# KeyBoard_LED.net
KiCad netlist of a schematic drawn in Altium Designer
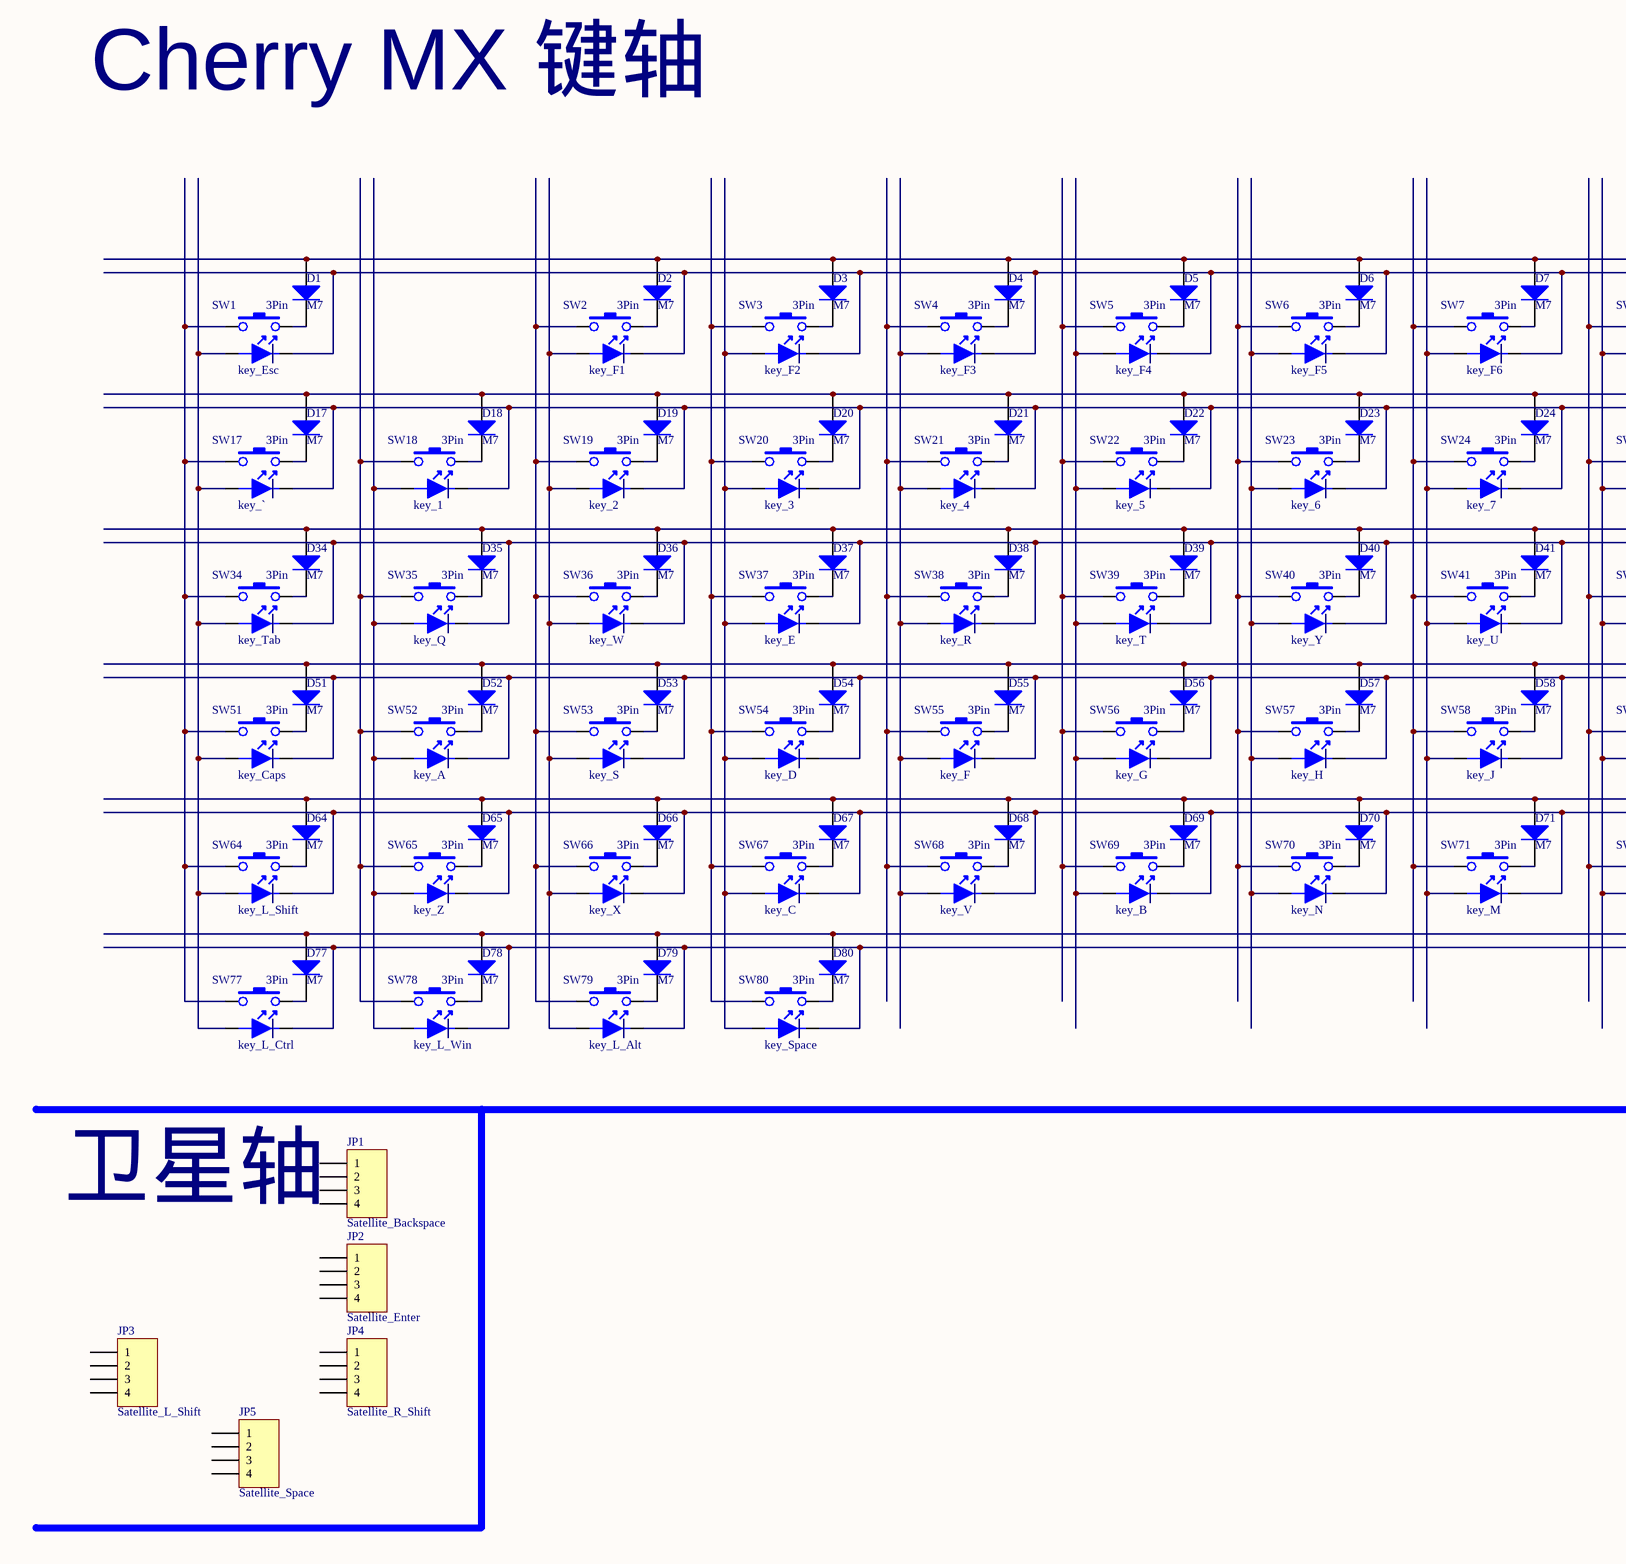
[diagram p0: KeyBoard_LED.SchDoc, left]
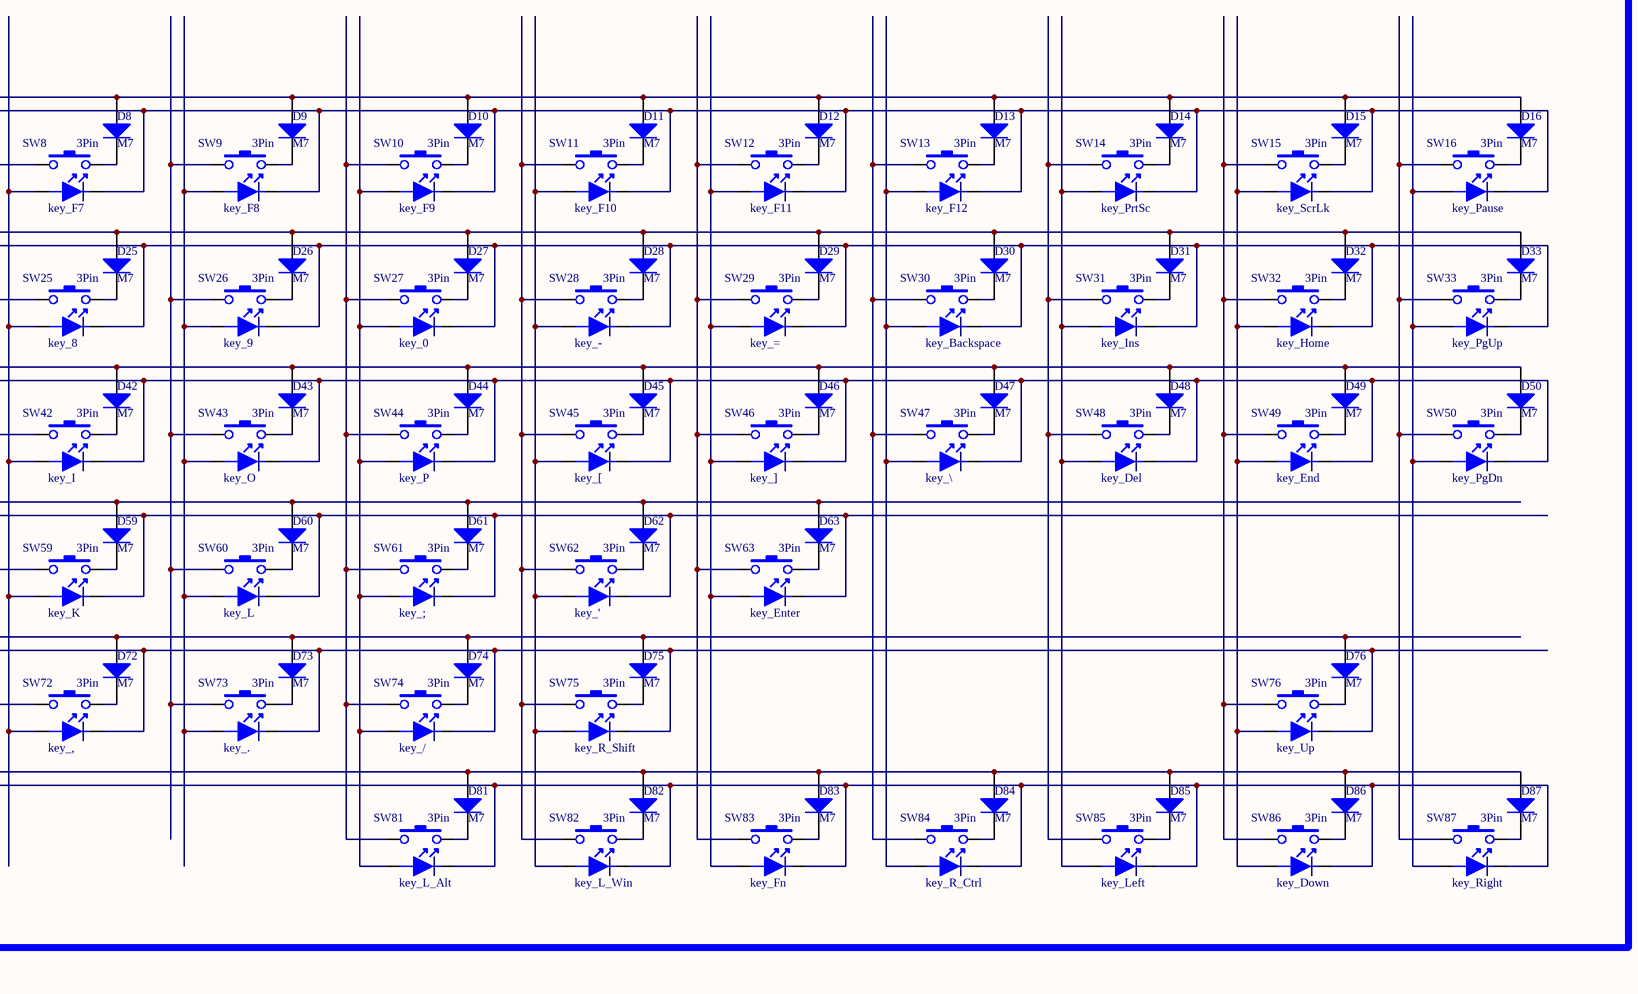
[diagram p1: KeyBoard_LED.SchDoc, right]

(export (version "E")
  (design (tool "Eeschema 10.0.6"))
  (components
    (comp (ref "D1")
      (value "M7")
      (footprint "SMA(DO-214AC)_S1")
      (description "二极管")
      (libsource (lib "Miscellaneous Devices LC") (part "SMA(DO-214AC) M7"))
    )
    (comp (ref "D2")
      (value "M7")
      (footprint "SMA(DO-214AC)_S1")
      (description "二极管")
      (libsource (lib "Miscellaneous Devices LC") (part "SMA(DO-214AC) M7"))
    )
    (comp (ref "D3")
      (value "M7")
      (footprint "SMA(DO-214AC)_S1")
      (description "二极管")
      (libsource (lib "Miscellaneous Devices LC") (part "SMA(DO-214AC) M7"))
    )
    (comp (ref "D4")
      (value "M7")
      (footprint "SMA(DO-214AC)_S1")
      (description "二极管")
      (libsource (lib "Miscellaneous Devices LC") (part "SMA(DO-214AC) M7"))
    )
    (comp (ref "D5")
      (value "M7")
      (footprint "SMA(DO-214AC)_S1")
      (description "二极管")
      (libsource (lib "Miscellaneous Devices LC") (part "SMA(DO-214AC) M7"))
    )
    (comp (ref "D6")
      (value "M7")
      (footprint "SMA(DO-214AC)_S1")
      (description "二极管")
      (libsource (lib "Miscellaneous Devices LC") (part "SMA(DO-214AC) M7"))
    )
    (comp (ref "D7")
      (value "M7")
      (footprint "SMA(DO-214AC)_S1")
      (description "二极管")
      (libsource (lib "Miscellaneous Devices LC") (part "SMA(DO-214AC) M7"))
    )
    (comp (ref "D8")
      (value "M7")
      (footprint "SMA(DO-214AC)_S1")
      (description "二极管")
      (libsource (lib "Miscellaneous Devices LC") (part "SMA(DO-214AC) M7"))
    )
    (comp (ref "D9")
      (value "M7")
      (footprint "SMA(DO-214AC)_S1")
      (description "二极管")
      (libsource (lib "Miscellaneous Devices LC") (part "SMA(DO-214AC) M7"))
    )
    (comp (ref "D10")
      (value "M7")
      (footprint "SMA(DO-214AC)_S1")
      (description "二极管")
      (libsource (lib "Miscellaneous Devices LC") (part "SMA(DO-214AC) M7"))
    )
    (comp (ref "D11")
      (value "M7")
      (footprint "SMA(DO-214AC)_S1")
      (description "二极管")
      (libsource (lib "Miscellaneous Devices LC") (part "SMA(DO-214AC) M7"))
    )
    (comp (ref "D12")
      (value "M7")
      (footprint "SMA(DO-214AC)_S1")
      (description "二极管")
      (libsource (lib "Miscellaneous Devices LC") (part "SMA(DO-214AC) M7"))
    )
    (comp (ref "D13")
      (value "M7")
      (footprint "SMA(DO-214AC)_S1")
      (description "二极管")
      (libsource (lib "Miscellaneous Devices LC") (part "SMA(DO-214AC) M7"))
    )
    (comp (ref "D14")
      (value "M7")
      (footprint "SMA(DO-214AC)_S1")
      (description "二极管")
      (libsource (lib "Miscellaneous Devices LC") (part "SMA(DO-214AC) M7"))
    )
    (comp (ref "D15")
      (value "M7")
      (footprint "SMA(DO-214AC)_S1")
      (description "二极管")
      (libsource (lib "Miscellaneous Devices LC") (part "SMA(DO-214AC) M7"))
    )
    (comp (ref "D16")
      (value "M7")
      (footprint "SMA(DO-214AC)_S1")
      (description "二极管")
      (libsource (lib "Miscellaneous Devices LC") (part "SMA(DO-214AC) M7"))
    )
    (comp (ref "D17")
      (value "M7")
      (footprint "SMA(DO-214AC)_S1")
      (description "二极管")
      (libsource (lib "Miscellaneous Devices LC") (part "SMA(DO-214AC) M7"))
    )
    (comp (ref "D18")
      (value "M7")
      (footprint "SMA(DO-214AC)_S1")
      (description "二极管")
      (libsource (lib "Miscellaneous Devices LC") (part "SMA(DO-214AC) M7"))
    )
    (comp (ref "D19")
      (value "M7")
      (footprint "SMA(DO-214AC)_S1")
      (description "二极管")
      (libsource (lib "Miscellaneous Devices LC") (part "SMA(DO-214AC) M7"))
    )
    (comp (ref "D20")
      (value "M7")
      (footprint "SMA(DO-214AC)_S1")
      (description "二极管")
      (libsource (lib "Miscellaneous Devices LC") (part "SMA(DO-214AC) M7"))
    )
    (comp (ref "D21")
      (value "M7")
      (footprint "SMA(DO-214AC)_S1")
      (description "二极管")
      (libsource (lib "Miscellaneous Devices LC") (part "SMA(DO-214AC) M7"))
    )
    (comp (ref "D22")
      (value "M7")
      (footprint "SMA(DO-214AC)_S1")
      (description "二极管")
      (libsource (lib "Miscellaneous Devices LC") (part "SMA(DO-214AC) M7"))
    )
    (comp (ref "D23")
      (value "M7")
      (footprint "SMA(DO-214AC)_S1")
      (description "二极管")
      (libsource (lib "Miscellaneous Devices LC") (part "SMA(DO-214AC) M7"))
    )
    (comp (ref "D24")
      (value "M7")
      (footprint "SMA(DO-214AC)_S1")
      (description "二极管")
      (libsource (lib "Miscellaneous Devices LC") (part "SMA(DO-214AC) M7"))
    )
    (comp (ref "D25")
      (value "M7")
      (footprint "SMA(DO-214AC)_S1")
      (description "二极管")
      (libsource (lib "Miscellaneous Devices LC") (part "SMA(DO-214AC) M7"))
    )
    (comp (ref "D26")
      (value "M7")
      (footprint "SMA(DO-214AC)_S1")
      (description "二极管")
      (libsource (lib "Miscellaneous Devices LC") (part "SMA(DO-214AC) M7"))
    )
    (comp (ref "D27")
      (value "M7")
      (footprint "SMA(DO-214AC)_S1")
      (description "二极管")
      (libsource (lib "Miscellaneous Devices LC") (part "SMA(DO-214AC) M7"))
    )
    (comp (ref "D28")
      (value "M7")
      (footprint "SMA(DO-214AC)_S1")
      (description "二极管")
      (libsource (lib "Miscellaneous Devices LC") (part "SMA(DO-214AC) M7"))
    )
    (comp (ref "D29")
      (value "M7")
      (footprint "SMA(DO-214AC)_S1")
      (description "二极管")
      (libsource (lib "Miscellaneous Devices LC") (part "SMA(DO-214AC) M7"))
    )
    (comp (ref "D30")
      (value "M7")
      (footprint "SMA(DO-214AC)_S1")
      (description "二极管")
      (libsource (lib "Miscellaneous Devices LC") (part "SMA(DO-214AC) M7"))
    )
    (comp (ref "D31")
      (value "M7")
      (footprint "SMA(DO-214AC)_S1")
      (description "二极管")
      (libsource (lib "Miscellaneous Devices LC") (part "SMA(DO-214AC) M7"))
    )
    (comp (ref "D32")
      (value "M7")
      (footprint "SMA(DO-214AC)_S1")
      (description "二极管")
      (libsource (lib "Miscellaneous Devices LC") (part "SMA(DO-214AC) M7"))
    )
    (comp (ref "D33")
      (value "M7")
      (footprint "SMA(DO-214AC)_S1")
      (description "二极管")
      (libsource (lib "Miscellaneous Devices LC") (part "SMA(DO-214AC) M7"))
    )
    (comp (ref "D34")
      (value "M7")
      (footprint "SMA(DO-214AC)_S1")
      (description "二极管")
      (libsource (lib "Miscellaneous Devices LC") (part "SMA(DO-214AC) M7"))
    )
    (comp (ref "D35")
      (value "M7")
      (footprint "SMA(DO-214AC)_S1")
      (description "二极管")
      (libsource (lib "Miscellaneous Devices LC") (part "SMA(DO-214AC) M7"))
    )
    (comp (ref "D36")
      (value "M7")
      (footprint "SMA(DO-214AC)_S1")
      (description "二极管")
      (libsource (lib "Miscellaneous Devices LC") (part "SMA(DO-214AC) M7"))
    )
    (comp (ref "D37")
      (value "M7")
      (footprint "SMA(DO-214AC)_S1")
      (description "二极管")
      (libsource (lib "Miscellaneous Devices LC") (part "SMA(DO-214AC) M7"))
    )
    (comp (ref "D38")
      (value "M7")
      (footprint "SMA(DO-214AC)_S1")
      (description "二极管")
      (libsource (lib "Miscellaneous Devices LC") (part "SMA(DO-214AC) M7"))
    )
    (comp (ref "D39")
      (value "M7")
      (footprint "SMA(DO-214AC)_S1")
      (description "二极管")
      (libsource (lib "Miscellaneous Devices LC") (part "SMA(DO-214AC) M7"))
    )
    (comp (ref "D40")
      (value "M7")
      (footprint "SMA(DO-214AC)_S1")
      (description "二极管")
      (libsource (lib "Miscellaneous Devices LC") (part "SMA(DO-214AC) M7"))
    )
    (comp (ref "D41")
      (value "M7")
      (footprint "SMA(DO-214AC)_S1")
      (description "二极管")
      (libsource (lib "Miscellaneous Devices LC") (part "SMA(DO-214AC) M7"))
    )
    (comp (ref "D42")
      (value "M7")
      (footprint "SMA(DO-214AC)_S1")
      (description "二极管")
      (libsource (lib "Miscellaneous Devices LC") (part "SMA(DO-214AC) M7"))
    )
    (comp (ref "D43")
      (value "M7")
      (footprint "SMA(DO-214AC)_S1")
      (description "二极管")
      (libsource (lib "Miscellaneous Devices LC") (part "SMA(DO-214AC) M7"))
    )
    (comp (ref "D44")
      (value "M7")
      (footprint "SMA(DO-214AC)_S1")
      (description "二极管")
      (libsource (lib "Miscellaneous Devices LC") (part "SMA(DO-214AC) M7"))
    )
    (comp (ref "D45")
      (value "M7")
      (footprint "SMA(DO-214AC)_S1")
      (description "二极管")
      (libsource (lib "Miscellaneous Devices LC") (part "SMA(DO-214AC) M7"))
    )
    (comp (ref "D46")
      (value "M7")
      (footprint "SMA(DO-214AC)_S1")
      (description "二极管")
      (libsource (lib "Miscellaneous Devices LC") (part "SMA(DO-214AC) M7"))
    )
    (comp (ref "D47")
      (value "M7")
      (footprint "SMA(DO-214AC)_S1")
      (description "二极管")
      (libsource (lib "Miscellaneous Devices LC") (part "SMA(DO-214AC) M7"))
    )
    (comp (ref "D48")
      (value "M7")
      (footprint "SMA(DO-214AC)_S1")
      (description "二极管")
      (libsource (lib "Miscellaneous Devices LC") (part "SMA(DO-214AC) M7"))
    )
    (comp (ref "D49")
      (value "M7")
      (footprint "SMA(DO-214AC)_S1")
      (description "二极管")
      (libsource (lib "Miscellaneous Devices LC") (part "SMA(DO-214AC) M7"))
    )
    (comp (ref "D50")
      (value "M7")
      (footprint "SMA(DO-214AC)_S1")
      (description "二极管")
      (libsource (lib "Miscellaneous Devices LC") (part "SMA(DO-214AC) M7"))
    )
    (comp (ref "D51")
      (value "M7")
      (footprint "SMA(DO-214AC)_S1")
      (description "二极管")
      (libsource (lib "Miscellaneous Devices LC") (part "SMA(DO-214AC) M7"))
    )
    (comp (ref "D52")
      (value "M7")
      (footprint "SMA(DO-214AC)_S1")
      (description "二极管")
      (libsource (lib "Miscellaneous Devices LC") (part "SMA(DO-214AC) M7"))
    )
    (comp (ref "D53")
      (value "M7")
      (footprint "SMA(DO-214AC)_S1")
      (description "二极管")
      (libsource (lib "Miscellaneous Devices LC") (part "SMA(DO-214AC) M7"))
    )
    (comp (ref "D54")
      (value "M7")
      (footprint "SMA(DO-214AC)_S1")
      (description "二极管")
      (libsource (lib "Miscellaneous Devices LC") (part "SMA(DO-214AC) M7"))
    )
    (comp (ref "D55")
      (value "M7")
      (footprint "SMA(DO-214AC)_S1")
      (description "二极管")
      (libsource (lib "Miscellaneous Devices LC") (part "SMA(DO-214AC) M7"))
    )
    (comp (ref "D56")
      (value "M7")
      (footprint "SMA(DO-214AC)_S1")
      (description "二极管")
      (libsource (lib "Miscellaneous Devices LC") (part "SMA(DO-214AC) M7"))
    )
    (comp (ref "D57")
      (value "M7")
      (footprint "SMA(DO-214AC)_S1")
      (description "二极管")
      (libsource (lib "Miscellaneous Devices LC") (part "SMA(DO-214AC) M7"))
    )
    (comp (ref "D58")
      (value "M7")
      (footprint "SMA(DO-214AC)_S1")
      (description "二极管")
      (libsource (lib "Miscellaneous Devices LC") (part "SMA(DO-214AC) M7"))
    )
    (comp (ref "D59")
      (value "M7")
      (footprint "SMA(DO-214AC)_S1")
      (description "二极管")
      (libsource (lib "Miscellaneous Devices LC") (part "SMA(DO-214AC) M7"))
    )
    (comp (ref "D60")
      (value "M7")
      (footprint "SMA(DO-214AC)_S1")
      (description "二极管")
      (libsource (lib "Miscellaneous Devices LC") (part "SMA(DO-214AC) M7"))
    )
    (comp (ref "D61")
      (value "M7")
      (footprint "SMA(DO-214AC)_S1")
      (description "二极管")
      (libsource (lib "Miscellaneous Devices LC") (part "SMA(DO-214AC) M7"))
    )
    (comp (ref "D62")
      (value "M7")
      (footprint "SMA(DO-214AC)_S1")
      (description "二极管")
      (libsource (lib "Miscellaneous Devices LC") (part "SMA(DO-214AC) M7"))
    )
    (comp (ref "D63")
      (value "M7")
      (footprint "SMA(DO-214AC)_S1")
      (description "二极管")
      (libsource (lib "Miscellaneous Devices LC") (part "SMA(DO-214AC) M7"))
    )
    (comp (ref "D64")
      (value "M7")
      (footprint "SMA(DO-214AC)_S1")
      (description "二极管")
      (libsource (lib "Miscellaneous Devices LC") (part "SMA(DO-214AC) M7"))
    )
    (comp (ref "D65")
      (value "M7")
      (footprint "SMA(DO-214AC)_S1")
      (description "二极管")
      (libsource (lib "Miscellaneous Devices LC") (part "SMA(DO-214AC) M7"))
    )
    (comp (ref "D66")
      (value "M7")
      (footprint "SMA(DO-214AC)_S1")
      (description "二极管")
      (libsource (lib "Miscellaneous Devices LC") (part "SMA(DO-214AC) M7"))
    )
    (comp (ref "D67")
      (value "M7")
      (footprint "SMA(DO-214AC)_S1")
      (description "二极管")
      (libsource (lib "Miscellaneous Devices LC") (part "SMA(DO-214AC) M7"))
    )
    (comp (ref "D68")
      (value "M7")
      (footprint "SMA(DO-214AC)_S1")
      (description "二极管")
      (libsource (lib "Miscellaneous Devices LC") (part "SMA(DO-214AC) M7"))
    )
    (comp (ref "D69")
      (value "M7")
      (footprint "SMA(DO-214AC)_S1")
      (description "二极管")
      (libsource (lib "Miscellaneous Devices LC") (part "SMA(DO-214AC) M7"))
    )
    (comp (ref "D70")
      (value "M7")
      (footprint "SMA(DO-214AC)_S1")
      (description "二极管")
      (libsource (lib "Miscellaneous Devices LC") (part "SMA(DO-214AC) M7"))
    )
    (comp (ref "D71")
      (value "M7")
      (footprint "SMA(DO-214AC)_S1")
      (description "二极管")
      (libsource (lib "Miscellaneous Devices LC") (part "SMA(DO-214AC) M7"))
    )
    (comp (ref "D72")
      (value "M7")
      (footprint "SMA(DO-214AC)_S1")
      (description "二极管")
      (libsource (lib "Miscellaneous Devices LC") (part "SMA(DO-214AC) M7"))
    )
    (comp (ref "D73")
      (value "M7")
      (footprint "SMA(DO-214AC)_S1")
      (description "二极管")
      (libsource (lib "Miscellaneous Devices LC") (part "SMA(DO-214AC) M7"))
    )
    (comp (ref "D74")
      (value "M7")
      (footprint "SMA(DO-214AC)_S1")
      (description "二极管")
      (libsource (lib "Miscellaneous Devices LC") (part "SMA(DO-214AC) M7"))
    )
    (comp (ref "D75")
      (value "M7")
      (footprint "SMA(DO-214AC)_S1")
      (description "二极管")
      (libsource (lib "Miscellaneous Devices LC") (part "SMA(DO-214AC) M7"))
    )
    (comp (ref "D76")
      (value "M7")
      (footprint "SMA(DO-214AC)_S1")
      (description "二极管")
      (libsource (lib "Miscellaneous Devices LC") (part "SMA(DO-214AC) M7"))
    )
    (comp (ref "D77")
      (value "M7")
      (footprint "SMA(DO-214AC)_S1")
      (description "二极管")
      (libsource (lib "Miscellaneous Devices LC") (part "SMA(DO-214AC) M7"))
    )
    (comp (ref "D78")
      (value "M7")
      (footprint "SMA(DO-214AC)_S1")
      (description "二极管")
      (libsource (lib "Miscellaneous Devices LC") (part "SMA(DO-214AC) M7"))
    )
    (comp (ref "D79")
      (value "M7")
      (footprint "SMA(DO-214AC)_S1")
      (description "二极管")
      (libsource (lib "Miscellaneous Devices LC") (part "SMA(DO-214AC) M7"))
    )
    (comp (ref "D80")
      (value "M7")
      (footprint "SMA(DO-214AC)_S1")
      (description "二极管")
      (libsource (lib "Miscellaneous Devices LC") (part "SMA(DO-214AC) M7"))
    )
    (comp (ref "D81")
      (value "M7")
      (footprint "SMA(DO-214AC)_S1")
      (description "二极管")
      (libsource (lib "Miscellaneous Devices LC") (part "SMA(DO-214AC) M7"))
    )
    (comp (ref "D82")
      (value "M7")
      (footprint "SMA(DO-214AC)_S1")
      (description "二极管")
      (libsource (lib "Miscellaneous Devices LC") (part "SMA(DO-214AC) M7"))
    )
    (comp (ref "D83")
      (value "M7")
      (footprint "SMA(DO-214AC)_S1")
      (description "二极管")
      (libsource (lib "Miscellaneous Devices LC") (part "SMA(DO-214AC) M7"))
    )
    (comp (ref "D84")
      (value "M7")
      (footprint "SMA(DO-214AC)_S1")
      (description "二极管")
      (libsource (lib "Miscellaneous Devices LC") (part "SMA(DO-214AC) M7"))
    )
    (comp (ref "D85")
      (value "M7")
      (footprint "SMA(DO-214AC)_S1")
      (description "二极管")
      (libsource (lib "Miscellaneous Devices LC") (part "SMA(DO-214AC) M7"))
    )
    (comp (ref "D86")
      (value "M7")
      (footprint "SMA(DO-214AC)_S1")
      (description "二极管")
      (libsource (lib "Miscellaneous Devices LC") (part "SMA(DO-214AC) M7"))
    )
    (comp (ref "D87")
      (value "M7")
      (footprint "SMA(DO-214AC)_S1")
      (description "二极管")
      (libsource (lib "Miscellaneous Devices LC") (part "SMA(DO-214AC) M7"))
    )
    (comp (ref "JP1")
      (value "Satellite_Backspace")
      (footprint "1x2")
      (description "Header, 4-Pin")
      (fields (field (name "PUBLISHER") "Altium Limited"))
      (libsource (lib "Miscellaneous Connectors") (part "Header 4"))
    )
    (comp (ref "JP2")
      (value "Satellite_Enter")
      (footprint "1x2")
      (description "Header, 4-Pin")
      (fields (field (name "PUBLISHER") "Altium Limited"))
      (libsource (lib "Miscellaneous Connectors") (part "Header 4"))
    )
    (comp (ref "JP3")
      (value "Satellite_L_Shift")
      (footprint "1x2")
      (description "Header, 4-Pin")
      (fields (field (name "PUBLISHER") "Altium Limited"))
      (libsource (lib "Miscellaneous Connectors") (part "Header 4"))
    )
    (comp (ref "JP4")
      (value "Satellite_R_Shift")
      (footprint "1x2")
      (description "Header, 4-Pin")
      (fields (field (name "PUBLISHER") "Altium Limited"))
      (libsource (lib "Miscellaneous Connectors") (part "Header 4"))
    )
    (comp (ref "JP5")
      (value "Satellite_Space")
      (footprint "1x6.25")
      (description "Header, 4-Pin")
      (fields (field (name "PUBLISHER") "Altium Limited"))
      (libsource (lib "Miscellaneous Connectors") (part "Header 4"))
    )
    (comp (ref "SW1")
      (value "key_Esc")
      (footprint "MX_SW_3_LED")
      (description "without Fixation pins  1-Pole w/LED")
      (libsource (lib "KeyBoard") (part "MX_SW_3_LED"))
    )
    (comp (ref "SW2")
      (value "key_F1")
      (footprint "MX_SW_3_LED")
      (description "without Fixation pins  1-Pole w/LED")
      (libsource (lib "KeyBoard") (part "MX_SW_3_LED"))
    )
    (comp (ref "SW3")
      (value "key_F2")
      (footprint "MX_SW_3_LED")
      (description "without Fixation pins  1-Pole w/LED")
      (libsource (lib "KeyBoard") (part "MX_SW_3_LED"))
    )
    (comp (ref "SW4")
      (value "key_F3")
      (footprint "MX_SW_3_LED")
      (description "without Fixation pins  1-Pole w/LED")
      (libsource (lib "KeyBoard") (part "MX_SW_3_LED"))
    )
    (comp (ref "SW5")
      (value "key_F4")
      (footprint "MX_SW_3_LED")
      (description "without Fixation pins  1-Pole w/LED")
      (libsource (lib "KeyBoard") (part "MX_SW_3_LED"))
    )
    (comp (ref "SW6")
      (value "key_F5")
      (footprint "MX_SW_3_LED")
      (description "without Fixation pins  1-Pole w/LED")
      (libsource (lib "KeyBoard") (part "MX_SW_3_LED"))
    )
    (comp (ref "SW7")
      (value "key_F6")
      (footprint "MX_SW_3_LED")
      (description "without Fixation pins  1-Pole w/LED")
      (libsource (lib "KeyBoard") (part "MX_SW_3_LED"))
    )
    (comp (ref "SW8")
      (value "key_F7")
      (footprint "MX_SW_3_LED")
      (description "without Fixation pins  1-Pole w/LED")
      (libsource (lib "KeyBoard") (part "MX_SW_3_LED"))
    )
    (comp (ref "SW9")
      (value "key_F8")
      (footprint "MX_SW_3_LED")
      (description "without Fixation pins  1-Pole w/LED")
      (libsource (lib "KeyBoard") (part "MX_SW_3_LED"))
    )
    (comp (ref "SW10")
      (value "key_F9")
      (footprint "MX_SW_3_LED")
      (description "without Fixation pins  1-Pole w/LED")
      (libsource (lib "KeyBoard") (part "MX_SW_3_LED"))
    )
    (comp (ref "SW11")
      (value "key_F10")
      (footprint "MX_SW_3_LED")
      (description "without Fixation pins  1-Pole w/LED")
      (libsource (lib "KeyBoard") (part "MX_SW_3_LED"))
    )
    (comp (ref "SW12")
      (value "key_F11")
      (footprint "MX_SW_3_LED")
      (description "without Fixation pins  1-Pole w/LED")
      (libsource (lib "KeyBoard") (part "MX_SW_3_LED"))
    )
    (comp (ref "SW13")
      (value "key_F12")
      (footprint "MX_SW_3_LED")
      (description "without Fixation pins  1-Pole w/LED")
      (libsource (lib "KeyBoard") (part "MX_SW_3_LED"))
    )
    (comp (ref "SW14")
      (value "key_PrtSc")
      (footprint "MX_SW_3_LED")
      (description "without Fixation pins  1-Pole w/LED")
      (libsource (lib "KeyBoard") (part "MX_SW_3_LED"))
    )
    (comp (ref "SW15")
      (value "key_ScrLk")
      (footprint "MX_SW_3_LED")
      (description "without Fixation pins  1-Pole w/LED")
      (libsource (lib "KeyBoard") (part "MX_SW_3_LED"))
    )
    (comp (ref "SW16")
      (value "key_Pause")
      (footprint "MX_SW_3_LED")
      (description "without Fixation pins  1-Pole w/LED")
      (libsource (lib "KeyBoard") (part "MX_SW_3_LED"))
    )
    (comp (ref "SW17")
      (value "key_`")
      (footprint "MX_SW_3_LED")
      (description "without Fixation pins  1-Pole w/LED")
      (libsource (lib "KeyBoard") (part "MX_SW_3_LED"))
    )
    (comp (ref "SW18")
      (value "key_1")
      (footprint "MX_SW_3_LED")
      (description "without Fixation pins  1-Pole w/LED")
      (libsource (lib "KeyBoard") (part "MX_SW_3_LED"))
    )
    (comp (ref "SW19")
      (value "key_2")
      (footprint "MX_SW_3_LED")
      (description "without Fixation pins  1-Pole w/LED")
      (libsource (lib "KeyBoard") (part "MX_SW_3_LED"))
    )
    (comp (ref "SW20")
      (value "key_3")
      (footprint "MX_SW_3_LED")
      (description "without Fixation pins  1-Pole w/LED")
      (libsource (lib "KeyBoard") (part "MX_SW_3_LED"))
    )
    (comp (ref "SW21")
      (value "key_4")
      (footprint "MX_SW_3_LED")
      (description "without Fixation pins  1-Pole w/LED")
      (libsource (lib "KeyBoard") (part "MX_SW_3_LED"))
    )
    (comp (ref "SW22")
      (value "key_5")
      (footprint "MX_SW_3_LED")
      (description "without Fixation pins  1-Pole w/LED")
      (libsource (lib "KeyBoard") (part "MX_SW_3_LED"))
    )
    (comp (ref "SW23")
      (value "key_6")
      (footprint "MX_SW_3_LED")
      (description "without Fixation pins  1-Pole w/LED")
      (libsource (lib "KeyBoard") (part "MX_SW_3_LED"))
    )
    (comp (ref "SW24")
      (value "key_7")
      (footprint "MX_SW_3_LED")
      (description "without Fixation pins  1-Pole w/LED")
      (libsource (lib "KeyBoard") (part "MX_SW_3_LED"))
    )
    (comp (ref "SW25")
      (value "key_8")
      (footprint "MX_SW_3_LED")
      (description "without Fixation pins  1-Pole w/LED")
      (libsource (lib "KeyBoard") (part "MX_SW_3_LED"))
    )
    (comp (ref "SW26")
      (value "key_9")
      (footprint "MX_SW_3_LED")
      (description "without Fixation pins  1-Pole w/LED")
      (libsource (lib "KeyBoard") (part "MX_SW_3_LED"))
    )
    (comp (ref "SW27")
      (value "key_0")
      (footprint "MX_SW_3_LED")
      (description "without Fixation pins  1-Pole w/LED")
      (libsource (lib "KeyBoard") (part "MX_SW_3_LED"))
    )
    (comp (ref "SW28")
      (value "key_-")
      (footprint "MX_SW_3_LED")
      (description "without Fixation pins  1-Pole w/LED")
      (libsource (lib "KeyBoard") (part "MX_SW_3_LED"))
    )
    (comp (ref "SW29")
      (value "key_=")
      (footprint "MX_SW_3_LED")
      (description "without Fixation pins  1-Pole w/LED")
      (libsource (lib "KeyBoard") (part "MX_SW_3_LED"))
    )
    (comp (ref "SW30")
      (value "key_Backspace")
      (footprint "MX_SW_3_LED")
      (description "without Fixation pins  1-Pole w/LED")
      (libsource (lib "KeyBoard") (part "MX_SW_3_LED"))
    )
    (comp (ref "SW31")
      (value "key_Ins")
      (footprint "MX_SW_3_LED")
      (description "without Fixation pins  1-Pole w/LED")
      (libsource (lib "KeyBoard") (part "MX_SW_3_LED"))
    )
    (comp (ref "SW32")
      (value "key_Home")
      (footprint "MX_SW_3_LED")
      (description "without Fixation pins  1-Pole w/LED")
      (libsource (lib "KeyBoard") (part "MX_SW_3_LED"))
    )
    (comp (ref "SW33")
      (value "key_PgUp")
      (footprint "MX_SW_3_LED")
      (description "without Fixation pins  1-Pole w/LED")
      (libsource (lib "KeyBoard") (part "MX_SW_3_LED"))
    )
    (comp (ref "SW34")
      (value "key_Tab")
      (footprint "MX_SW_3_LED")
      (description "without Fixation pins  1-Pole w/LED")
      (libsource (lib "KeyBoard") (part "MX_SW_3_LED"))
    )
    (comp (ref "SW35")
      (value "key_Q")
      (footprint "MX_SW_3_LED")
      (description "without Fixation pins  1-Pole w/LED")
      (libsource (lib "KeyBoard") (part "MX_SW_3_LED"))
    )
    (comp (ref "SW36")
      (value "key_W")
      (footprint "MX_SW_3_LED")
      (description "without Fixation pins  1-Pole w/LED")
      (libsource (lib "KeyBoard") (part "MX_SW_3_LED"))
    )
    (comp (ref "SW37")
      (value "key_E")
      (footprint "MX_SW_3_LED")
      (description "without Fixation pins  1-Pole w/LED")
      (libsource (lib "KeyBoard") (part "MX_SW_3_LED"))
    )
    (comp (ref "SW38")
      (value "key_R")
      (footprint "MX_SW_3_LED")
      (description "without Fixation pins  1-Pole w/LED")
      (libsource (lib "KeyBoard") (part "MX_SW_3_LED"))
    )
    (comp (ref "SW39")
      (value "key_T")
      (footprint "MX_SW_3_LED")
      (description "without Fixation pins  1-Pole w/LED")
      (libsource (lib "KeyBoard") (part "MX_SW_3_LED"))
    )
    (comp (ref "SW40")
      (value "key_Y")
      (footprint "MX_SW_3_LED")
      (description "without Fixation pins  1-Pole w/LED")
      (libsource (lib "KeyBoard") (part "MX_SW_3_LED"))
    )
    (comp (ref "SW41")
      (value "key_U")
      (footprint "MX_SW_3_LED")
      (description "without Fixation pins  1-Pole w/LED")
      (libsource (lib "KeyBoard") (part "MX_SW_3_LED"))
    )
    (comp (ref "SW42")
      (value "key_I")
      (footprint "MX_SW_3_LED")
      (description "without Fixation pins  1-Pole w/LED")
      (libsource (lib "KeyBoard") (part "MX_SW_3_LED"))
    )
    (comp (ref "SW43")
      (value "key_O")
      (footprint "MX_SW_3_LED")
      (description "without Fixation pins  1-Pole w/LED")
      (libsource (lib "KeyBoard") (part "MX_SW_3_LED"))
    )
    (comp (ref "SW44")
      (value "key_P")
      (footprint "MX_SW_3_LED")
      (description "without Fixation pins  1-Pole w/LED")
      (libsource (lib "KeyBoard") (part "MX_SW_3_LED"))
    )
    (comp (ref "SW45")
      (value "key_[")
      (footprint "MX_SW_3_LED")
      (description "without Fixation pins  1-Pole w/LED")
      (libsource (lib "KeyBoard") (part "MX_SW_3_LED"))
    )
    (comp (ref "SW46")
      (value "key_]")
      (footprint "MX_SW_3_LED")
      (description "without Fixation pins  1-Pole w/LED")
      (libsource (lib "KeyBoard") (part "MX_SW_3_LED"))
    )
    (comp (ref "SW47")
      (value "key~{_}")
      (footprint "MX_SW_3_LED")
      (description "without Fixation pins  1-Pole w/LED")
      (libsource (lib "KeyBoard") (part "MX_SW_3_LED"))
    )
    (comp (ref "SW48")
      (value "key_Del")
      (footprint "MX_SW_3_LED")
      (description "without Fixation pins  1-Pole w/LED")
      (libsource (lib "KeyBoard") (part "MX_SW_3_LED"))
    )
    (comp (ref "SW49")
      (value "key_End")
      (footprint "MX_SW_3_LED")
      (description "without Fixation pins  1-Pole w/LED")
      (libsource (lib "KeyBoard") (part "MX_SW_3_LED"))
    )
    (comp (ref "SW50")
      (value "key_PgDn")
      (footprint "MX_SW_3_LED")
      (description "without Fixation pins  1-Pole w/LED")
      (libsource (lib "KeyBoard") (part "MX_SW_3_LED"))
    )
    (comp (ref "SW51")
      (value "key_Caps")
      (footprint "MX_SW_3_LED")
      (description "without Fixation pins  1-Pole w/LED")
      (libsource (lib "KeyBoard") (part "MX_SW_3_LED"))
    )
    (comp (ref "SW52")
      (value "key_A")
      (footprint "MX_SW_3_LED")
      (description "without Fixation pins  1-Pole w/LED")
      (libsource (lib "KeyBoard") (part "MX_SW_3_LED"))
    )
    (comp (ref "SW53")
      (value "key_S")
      (footprint "MX_SW_3_LED")
      (description "without Fixation pins  1-Pole w/LED")
      (libsource (lib "KeyBoard") (part "MX_SW_3_LED"))
    )
    (comp (ref "SW54")
      (value "key_D")
      (footprint "MX_SW_3_LED")
      (description "without Fixation pins  1-Pole w/LED")
      (libsource (lib "KeyBoard") (part "MX_SW_3_LED"))
    )
    (comp (ref "SW55")
      (value "key_F")
      (footprint "MX_SW_3_LED")
      (description "without Fixation pins  1-Pole w/LED")
      (libsource (lib "KeyBoard") (part "MX_SW_3_LED"))
    )
    (comp (ref "SW56")
      (value "key_G")
      (footprint "MX_SW_3_LED")
      (description "without Fixation pins  1-Pole w/LED")
      (libsource (lib "KeyBoard") (part "MX_SW_3_LED"))
    )
    (comp (ref "SW57")
      (value "key_H")
      (footprint "MX_SW_3_LED")
      (description "without Fixation pins  1-Pole w/LED")
      (libsource (lib "KeyBoard") (part "MX_SW_3_LED"))
    )
    (comp (ref "SW58")
      (value "key_J")
      (footprint "MX_SW_3_LED")
      (description "without Fixation pins  1-Pole w/LED")
      (libsource (lib "KeyBoard") (part "MX_SW_3_LED"))
    )
    (comp (ref "SW59")
      (value "key_K")
      (footprint "MX_SW_3_LED")
      (description "without Fixation pins  1-Pole w/LED")
      (libsource (lib "KeyBoard") (part "MX_SW_3_LED"))
    )
    (comp (ref "SW60")
      (value "key_L")
      (footprint "MX_SW_3_LED")
      (description "without Fixation pins  1-Pole w/LED")
      (libsource (lib "KeyBoard") (part "MX_SW_3_LED"))
    )
    (comp (ref "SW61")
      (value "key_;")
      (footprint "MX_SW_3_LED")
      (description "without Fixation pins  1-Pole w/LED")
      (libsource (lib "KeyBoard") (part "MX_SW_3_LED"))
    )
    (comp (ref "SW62")
      (value "key_'")
      (footprint "MX_SW_3_LED")
      (description "without Fixation pins  1-Pole w/LED")
      (libsource (lib "KeyBoard") (part "MX_SW_3_LED"))
    )
    (comp (ref "SW63")
      (value "key_Enter")
      (footprint "MX_SW_3_LED")
      (description "without Fixation pins  1-Pole w/LED")
      (libsource (lib "KeyBoard") (part "MX_SW_3_LED"))
    )
    (comp (ref "SW64")
      (value "key_L_Shift")
      (footprint "MX_SW_3_LED")
      (description "without Fixation pins  1-Pole w/LED")
      (libsource (lib "KeyBoard") (part "MX_SW_3_LED"))
    )
    (comp (ref "SW65")
      (value "key_Z")
      (footprint "MX_SW_3_LED")
      (description "without Fixation pins  1-Pole w/LED")
      (libsource (lib "KeyBoard") (part "MX_SW_3_LED"))
    )
    (comp (ref "SW66")
      (value "key_X")
      (footprint "MX_SW_3_LED")
      (description "without Fixation pins  1-Pole w/LED")
      (libsource (lib "KeyBoard") (part "MX_SW_3_LED"))
    )
    (comp (ref "SW67")
      (value "key_C")
      (footprint "MX_SW_3_LED")
      (description "without Fixation pins  1-Pole w/LED")
      (libsource (lib "KeyBoard") (part "MX_SW_3_LED"))
    )
    (comp (ref "SW68")
      (value "key_V")
      (footprint "MX_SW_3_LED")
      (description "without Fixation pins  1-Pole w/LED")
      (libsource (lib "KeyBoard") (part "MX_SW_3_LED"))
    )
    (comp (ref "SW69")
      (value "key_B")
      (footprint "MX_SW_3_LED")
      (description "without Fixation pins  1-Pole w/LED")
      (libsource (lib "KeyBoard") (part "MX_SW_3_LED"))
    )
    (comp (ref "SW70")
      (value "key_N")
      (footprint "MX_SW_3_LED")
      (description "without Fixation pins  1-Pole w/LED")
      (libsource (lib "KeyBoard") (part "MX_SW_3_LED"))
    )
    (comp (ref "SW71")
      (value "key_M")
      (footprint "MX_SW_3_LED")
      (description "without Fixation pins  1-Pole w/LED")
      (libsource (lib "KeyBoard") (part "MX_SW_3_LED"))
    )
    (comp (ref "SW72")
      (value "key_,")
      (footprint "MX_SW_3_LED")
      (description "without Fixation pins  1-Pole w/LED")
      (libsource (lib "KeyBoard") (part "MX_SW_3_LED"))
    )
    (comp (ref "SW73")
      (value "key_.")
      (footprint "MX_SW_3_LED")
      (description "without Fixation pins  1-Pole w/LED")
      (libsource (lib "KeyBoard") (part "MX_SW_3_LED"))
    )
    (comp (ref "SW74")
      (value "key_/")
      (footprint "MX_SW_3_LED")
      (description "without Fixation pins  1-Pole w/LED")
      (libsource (lib "KeyBoard") (part "MX_SW_3_LED"))
    )
    (comp (ref "SW75")
      (value "key_R_Shift")
      (footprint "MX_SW_3_LED")
      (description "without Fixation pins  1-Pole w/LED")
      (libsource (lib "KeyBoard") (part "MX_SW_3_LED"))
    )
    (comp (ref "SW76")
      (value "key_Up")
      (footprint "MX_SW_3_LED")
      (description "without Fixation pins  1-Pole w/LED")
      (libsource (lib "KeyBoard") (part "MX_SW_3_LED"))
    )
    (comp (ref "SW77")
      (value "key_L_Ctrl")
      (footprint "MX_SW_3_LED")
      (description "without Fixation pins  1-Pole w/LED")
      (libsource (lib "KeyBoard") (part "MX_SW_3_LED"))
    )
    (comp (ref "SW78")
      (value "key_L_Win")
      (footprint "MX_SW_3_LED")
      (description "without Fixation pins  1-Pole w/LED")
      (libsource (lib "KeyBoard") (part "MX_SW_3_LED"))
    )
    (comp (ref "SW79")
      (value "key_L_Alt")
      (footprint "MX_SW_3_LED")
      (description "without Fixation pins  1-Pole w/LED")
      (libsource (lib "KeyBoard") (part "MX_SW_3_LED"))
    )
    (comp (ref "SW80")
      (value "key_Space")
      (footprint "MX_SW_3_LED")
      (description "without Fixation pins  1-Pole w/LED")
      (libsource (lib "KeyBoard") (part "MX_SW_3_LED"))
    )
    (comp (ref "SW81")
      (value "key_L_Alt")
      (footprint "MX_SW_3_LED")
      (description "without Fixation pins  1-Pole w/LED")
      (libsource (lib "KeyBoard") (part "MX_SW_3_LED"))
    )
    (comp (ref "SW82")
      (value "key_L_Win")
      (footprint "MX_SW_3_LED")
      (description "without Fixation pins  1-Pole w/LED")
      (libsource (lib "KeyBoard") (part "MX_SW_3_LED"))
    )
    (comp (ref "SW83")
      (value "key_Fn")
      (footprint "MX_SW_3_LED")
      (description "without Fixation pins  1-Pole w/LED")
      (libsource (lib "KeyBoard") (part "MX_SW_3_LED"))
    )
    (comp (ref "SW84")
      (value "key_R_Ctrl")
      (footprint "MX_SW_3_LED")
      (description "without Fixation pins  1-Pole w/LED")
      (libsource (lib "KeyBoard") (part "MX_SW_3_LED"))
    )
    (comp (ref "SW85")
      (value "key_Left")
      (footprint "MX_SW_3_LED")
      (description "without Fixation pins  1-Pole w/LED")
      (libsource (lib "KeyBoard") (part "MX_SW_3_LED"))
    )
    (comp (ref "SW86")
      (value "key_Down")
      (footprint "MX_SW_3_LED")
      (description "without Fixation pins  1-Pole w/LED")
      (libsource (lib "KeyBoard") (part "MX_SW_3_LED"))
    )
    (comp (ref "SW87")
      (value "key_Right")
      (footprint "MX_SW_3_LED")
      (description "without Fixation pins  1-Pole w/LED")
      (libsource (lib "KeyBoard") (part "MX_SW_3_LED"))
    )
  )
  (nets
    (net (code "1") (name "Net-(D1-A)") (class "Default")
      (node (ref "D1") (pin "1") (pinfunction "A_1") (pintype "passive"))
      (node (ref "D10") (pin "1") (pinfunction "A_1") (pintype "passive"))
      (node (ref "D11") (pin "1") (pinfunction "A_1") (pintype "passive"))
      (node (ref "D12") (pin "1") (pinfunction "A_1") (pintype "passive"))
      (node (ref "D13") (pin "1") (pinfunction "A_1") (pintype "passive"))
      (node (ref "D14") (pin "1") (pinfunction "A_1") (pintype "passive"))
      (node (ref "D15") (pin "1") (pinfunction "A_1") (pintype "passive"))
      (node (ref "D16") (pin "1") (pinfunction "A_1") (pintype "passive"))
      (node (ref "D2") (pin "1") (pinfunction "A_1") (pintype "passive"))
      (node (ref "D3") (pin "1") (pinfunction "A_1") (pintype "passive"))
      (node (ref "D4") (pin "1") (pinfunction "A_1") (pintype "passive"))
      (node (ref "D5") (pin "1") (pinfunction "A_1") (pintype "passive"))
      (node (ref "D6") (pin "1") (pinfunction "A_1") (pintype "passive"))
      (node (ref "D7") (pin "1") (pinfunction "A_1") (pintype "passive"))
      (node (ref "D8") (pin "1") (pinfunction "A_1") (pintype "passive"))
      (node (ref "D9") (pin "1") (pinfunction "A_1") (pintype "passive"))
    )
    (net (code "2") (name "Net-(D1-K)") (class "Default")
      (node (ref "D1") (pin "2") (pinfunction "K_2") (pintype "passive"))
      (node (ref "SW1") (pin "2") (pinfunction "2_2") (pintype "passive"))
    )
    (net (code "3") (name "Net-(D2-K)") (class "Default")
      (node (ref "D2") (pin "2") (pinfunction "K_2") (pintype "passive"))
      (node (ref "SW2") (pin "2") (pinfunction "2_2") (pintype "passive"))
    )
    (net (code "4") (name "Net-(D3-K)") (class "Default")
      (node (ref "D3") (pin "2") (pinfunction "K_2") (pintype "passive"))
      (node (ref "SW3") (pin "2") (pinfunction "2_2") (pintype "passive"))
    )
    (net (code "5") (name "Net-(D4-K)") (class "Default")
      (node (ref "D4") (pin "2") (pinfunction "K_2") (pintype "passive"))
      (node (ref "SW4") (pin "2") (pinfunction "2_2") (pintype "passive"))
    )
    (net (code "6") (name "Net-(D5-K)") (class "Default")
      (node (ref "D5") (pin "2") (pinfunction "K_2") (pintype "passive"))
      (node (ref "SW5") (pin "2") (pinfunction "2_2") (pintype "passive"))
    )
    (net (code "7") (name "Net-(D6-K)") (class "Default")
      (node (ref "D6") (pin "2") (pinfunction "K_2") (pintype "passive"))
      (node (ref "SW6") (pin "2") (pinfunction "2_2") (pintype "passive"))
    )
    (net (code "8") (name "Net-(D7-K)") (class "Default")
      (node (ref "D7") (pin "2") (pinfunction "K_2") (pintype "passive"))
      (node (ref "SW7") (pin "2") (pinfunction "2_2") (pintype "passive"))
    )
    (net (code "9") (name "Net-(D8-K)") (class "Default")
      (node (ref "D8") (pin "2") (pinfunction "K_2") (pintype "passive"))
      (node (ref "SW8") (pin "2") (pinfunction "2_2") (pintype "passive"))
    )
    (net (code "10") (name "Net-(D9-K)") (class "Default")
      (node (ref "D9") (pin "2") (pinfunction "K_2") (pintype "passive"))
      (node (ref "SW9") (pin "2") (pinfunction "2_2") (pintype "passive"))
    )
    (net (code "11") (name "Net-(D10-K)") (class "Default")
      (node (ref "D10") (pin "2") (pinfunction "K_2") (pintype "passive"))
      (node (ref "SW10") (pin "2") (pinfunction "2_2") (pintype "passive"))
    )
    (net (code "12") (name "Net-(D11-K)") (class "Default")
      (node (ref "D11") (pin "2") (pinfunction "K_2") (pintype "passive"))
      (node (ref "SW11") (pin "2") (pinfunction "2_2") (pintype "passive"))
    )
    (net (code "13") (name "Net-(D12-K)") (class "Default")
      (node (ref "D12") (pin "2") (pinfunction "K_2") (pintype "passive"))
      (node (ref "SW12") (pin "2") (pinfunction "2_2") (pintype "passive"))
    )
    (net (code "14") (name "Net-(D13-K)") (class "Default")
      (node (ref "D13") (pin "2") (pinfunction "K_2") (pintype "passive"))
      (node (ref "SW13") (pin "2") (pinfunction "2_2") (pintype "passive"))
    )
    (net (code "15") (name "Net-(D14-K)") (class "Default")
      (node (ref "D14") (pin "2") (pinfunction "K_2") (pintype "passive"))
      (node (ref "SW14") (pin "2") (pinfunction "2_2") (pintype "passive"))
    )
    (net (code "16") (name "Net-(D15-K)") (class "Default")
      (node (ref "D15") (pin "2") (pinfunction "K_2") (pintype "passive"))
      (node (ref "SW15") (pin "2") (pinfunction "2_2") (pintype "passive"))
    )
    (net (code "17") (name "Net-(D16-K)") (class "Default")
      (node (ref "D16") (pin "2") (pinfunction "K_2") (pintype "passive"))
      (node (ref "SW16") (pin "2") (pinfunction "2_2") (pintype "passive"))
    )
    (net (code "18") (name "Net-(D17-A)") (class "Default")
      (node (ref "D17") (pin "1") (pinfunction "A_1") (pintype "passive"))
      (node (ref "D18") (pin "1") (pinfunction "A_1") (pintype "passive"))
      (node (ref "D19") (pin "1") (pinfunction "A_1") (pintype "passive"))
      (node (ref "D20") (pin "1") (pinfunction "A_1") (pintype "passive"))
      (node (ref "D21") (pin "1") (pinfunction "A_1") (pintype "passive"))
      (node (ref "D22") (pin "1") (pinfunction "A_1") (pintype "passive"))
      (node (ref "D23") (pin "1") (pinfunction "A_1") (pintype "passive"))
      (node (ref "D24") (pin "1") (pinfunction "A_1") (pintype "passive"))
      (node (ref "D25") (pin "1") (pinfunction "A_1") (pintype "passive"))
      (node (ref "D26") (pin "1") (pinfunction "A_1") (pintype "passive"))
      (node (ref "D27") (pin "1") (pinfunction "A_1") (pintype "passive"))
      (node (ref "D28") (pin "1") (pinfunction "A_1") (pintype "passive"))
      (node (ref "D29") (pin "1") (pinfunction "A_1") (pintype "passive"))
      (node (ref "D30") (pin "1") (pinfunction "A_1") (pintype "passive"))
      (node (ref "D31") (pin "1") (pinfunction "A_1") (pintype "passive"))
      (node (ref "D32") (pin "1") (pinfunction "A_1") (pintype "passive"))
      (node (ref "D33") (pin "1") (pinfunction "A_1") (pintype "passive"))
    )
    (net (code "19") (name "Net-(D17-K)") (class "Default")
      (node (ref "D17") (pin "2") (pinfunction "K_2") (pintype "passive"))
      (node (ref "SW17") (pin "2") (pinfunction "2_2") (pintype "passive"))
    )
    (net (code "20") (name "Net-(D18-K)") (class "Default")
      (node (ref "D18") (pin "2") (pinfunction "K_2") (pintype "passive"))
      (node (ref "SW18") (pin "2") (pinfunction "2_2") (pintype "passive"))
    )
    (net (code "21") (name "Net-(D19-K)") (class "Default")
      (node (ref "D19") (pin "2") (pinfunction "K_2") (pintype "passive"))
      (node (ref "SW19") (pin "2") (pinfunction "2_2") (pintype "passive"))
    )
    (net (code "22") (name "Net-(D20-K)") (class "Default")
      (node (ref "D20") (pin "2") (pinfunction "K_2") (pintype "passive"))
      (node (ref "SW20") (pin "2") (pinfunction "2_2") (pintype "passive"))
    )
    (net (code "23") (name "Net-(D21-K)") (class "Default")
      (node (ref "D21") (pin "2") (pinfunction "K_2") (pintype "passive"))
      (node (ref "SW21") (pin "2") (pinfunction "2_2") (pintype "passive"))
    )
    (net (code "24") (name "Net-(D22-K)") (class "Default")
      (node (ref "D22") (pin "2") (pinfunction "K_2") (pintype "passive"))
      (node (ref "SW22") (pin "2") (pinfunction "2_2") (pintype "passive"))
    )
    (net (code "25") (name "Net-(D23-K)") (class "Default")
      (node (ref "D23") (pin "2") (pinfunction "K_2") (pintype "passive"))
      (node (ref "SW23") (pin "2") (pinfunction "2_2") (pintype "passive"))
    )
    (net (code "26") (name "Net-(D24-K)") (class "Default")
      (node (ref "D24") (pin "2") (pinfunction "K_2") (pintype "passive"))
      (node (ref "SW24") (pin "2") (pinfunction "2_2") (pintype "passive"))
    )
    (net (code "27") (name "Net-(D25-K)") (class "Default")
      (node (ref "D25") (pin "2") (pinfunction "K_2") (pintype "passive"))
      (node (ref "SW25") (pin "2") (pinfunction "2_2") (pintype "passive"))
    )
    (net (code "28") (name "Net-(D26-K)") (class "Default")
      (node (ref "D26") (pin "2") (pinfunction "K_2") (pintype "passive"))
      (node (ref "SW26") (pin "2") (pinfunction "2_2") (pintype "passive"))
    )
    (net (code "29") (name "Net-(D27-K)") (class "Default")
      (node (ref "D27") (pin "2") (pinfunction "K_2") (pintype "passive"))
      (node (ref "SW27") (pin "2") (pinfunction "2_2") (pintype "passive"))
    )
    (net (code "30") (name "Net-(D28-K)") (class "Default")
      (node (ref "D28") (pin "2") (pinfunction "K_2") (pintype "passive"))
      (node (ref "SW28") (pin "2") (pinfunction "2_2") (pintype "passive"))
    )
    (net (code "31") (name "Net-(D29-K)") (class "Default")
      (node (ref "D29") (pin "2") (pinfunction "K_2") (pintype "passive"))
      (node (ref "SW29") (pin "2") (pinfunction "2_2") (pintype "passive"))
    )
    (net (code "32") (name "Net-(D30-K)") (class "Default")
      (node (ref "D30") (pin "2") (pinfunction "K_2") (pintype "passive"))
      (node (ref "SW30") (pin "2") (pinfunction "2_2") (pintype "passive"))
    )
    (net (code "33") (name "Net-(D31-K)") (class "Default")
      (node (ref "D31") (pin "2") (pinfunction "K_2") (pintype "passive"))
      (node (ref "SW31") (pin "2") (pinfunction "2_2") (pintype "passive"))
    )
    (net (code "34") (name "Net-(D32-K)") (class "Default")
      (node (ref "D32") (pin "2") (pinfunction "K_2") (pintype "passive"))
      (node (ref "SW32") (pin "2") (pinfunction "2_2") (pintype "passive"))
    )
    (net (code "35") (name "Net-(D33-K)") (class "Default")
      (node (ref "D33") (pin "2") (pinfunction "K_2") (pintype "passive"))
      (node (ref "SW33") (pin "2") (pinfunction "2_2") (pintype "passive"))
    )
    (net (code "36") (name "Net-(D34-A)") (class "Default")
      (node (ref "D34") (pin "1") (pinfunction "A_1") (pintype "passive"))
      (node (ref "D35") (pin "1") (pinfunction "A_1") (pintype "passive"))
      (node (ref "D36") (pin "1") (pinfunction "A_1") (pintype "passive"))
      (node (ref "D37") (pin "1") (pinfunction "A_1") (pintype "passive"))
      (node (ref "D38") (pin "1") (pinfunction "A_1") (pintype "passive"))
      (node (ref "D39") (pin "1") (pinfunction "A_1") (pintype "passive"))
      (node (ref "D40") (pin "1") (pinfunction "A_1") (pintype "passive"))
      (node (ref "D41") (pin "1") (pinfunction "A_1") (pintype "passive"))
      (node (ref "D42") (pin "1") (pinfunction "A_1") (pintype "passive"))
      (node (ref "D43") (pin "1") (pinfunction "A_1") (pintype "passive"))
      (node (ref "D44") (pin "1") (pinfunction "A_1") (pintype "passive"))
      (node (ref "D45") (pin "1") (pinfunction "A_1") (pintype "passive"))
      (node (ref "D46") (pin "1") (pinfunction "A_1") (pintype "passive"))
      (node (ref "D47") (pin "1") (pinfunction "A_1") (pintype "passive"))
      (node (ref "D48") (pin "1") (pinfunction "A_1") (pintype "passive"))
      (node (ref "D49") (pin "1") (pinfunction "A_1") (pintype "passive"))
      (node (ref "D50") (pin "1") (pinfunction "A_1") (pintype "passive"))
    )
    (net (code "37") (name "Net-(D34-K)") (class "Default")
      (node (ref "D34") (pin "2") (pinfunction "K_2") (pintype "passive"))
      (node (ref "SW34") (pin "2") (pinfunction "2_2") (pintype "passive"))
    )
    (net (code "38") (name "Net-(D35-K)") (class "Default")
      (node (ref "D35") (pin "2") (pinfunction "K_2") (pintype "passive"))
      (node (ref "SW35") (pin "2") (pinfunction "2_2") (pintype "passive"))
    )
    (net (code "39") (name "Net-(D36-K)") (class "Default")
      (node (ref "D36") (pin "2") (pinfunction "K_2") (pintype "passive"))
      (node (ref "SW36") (pin "2") (pinfunction "2_2") (pintype "passive"))
    )
    (net (code "40") (name "Net-(D37-K)") (class "Default")
      (node (ref "D37") (pin "2") (pinfunction "K_2") (pintype "passive"))
      (node (ref "SW37") (pin "2") (pinfunction "2_2") (pintype "passive"))
    )
    (net (code "41") (name "Net-(D38-K)") (class "Default")
      (node (ref "D38") (pin "2") (pinfunction "K_2") (pintype "passive"))
      (node (ref "SW38") (pin "2") (pinfunction "2_2") (pintype "passive"))
    )
    (net (code "42") (name "Net-(D39-K)") (class "Default")
      (node (ref "D39") (pin "2") (pinfunction "K_2") (pintype "passive"))
      (node (ref "SW39") (pin "2") (pinfunction "2_2") (pintype "passive"))
    )
    (net (code "43") (name "Net-(D40-K)") (class "Default")
      (node (ref "D40") (pin "2") (pinfunction "K_2") (pintype "passive"))
      (node (ref "SW40") (pin "2") (pinfunction "2_2") (pintype "passive"))
    )
    (net (code "44") (name "Net-(D41-K)") (class "Default")
      (node (ref "D41") (pin "2") (pinfunction "K_2") (pintype "passive"))
      (node (ref "SW41") (pin "2") (pinfunction "2_2") (pintype "passive"))
    )
    (net (code "45") (name "Net-(D42-K)") (class "Default")
      (node (ref "D42") (pin "2") (pinfunction "K_2") (pintype "passive"))
      (node (ref "SW42") (pin "2") (pinfunction "2_2") (pintype "passive"))
    )
    (net (code "46") (name "Net-(D43-K)") (class "Default")
      (node (ref "D43") (pin "2") (pinfunction "K_2") (pintype "passive"))
      (node (ref "SW43") (pin "2") (pinfunction "2_2") (pintype "passive"))
    )
    (net (code "47") (name "Net-(D44-K)") (class "Default")
      (node (ref "D44") (pin "2") (pinfunction "K_2") (pintype "passive"))
      (node (ref "SW44") (pin "2") (pinfunction "2_2") (pintype "passive"))
    )
    (net (code "48") (name "Net-(D45-K)") (class "Default")
      (node (ref "D45") (pin "2") (pinfunction "K_2") (pintype "passive"))
      (node (ref "SW45") (pin "2") (pinfunction "2_2") (pintype "passive"))
    )
    (net (code "49") (name "Net-(D46-K)") (class "Default")
      (node (ref "D46") (pin "2") (pinfunction "K_2") (pintype "passive"))
      (node (ref "SW46") (pin "2") (pinfunction "2_2") (pintype "passive"))
    )
    (net (code "50") (name "Net-(D47-K)") (class "Default")
      (node (ref "D47") (pin "2") (pinfunction "K_2") (pintype "passive"))
      (node (ref "SW47") (pin "2") (pinfunction "2_2") (pintype "passive"))
    )
    (net (code "51") (name "Net-(D48-K)") (class "Default")
      (node (ref "D48") (pin "2") (pinfunction "K_2") (pintype "passive"))
      (node (ref "SW48") (pin "2") (pinfunction "2_2") (pintype "passive"))
    )
    (net (code "52") (name "Net-(D49-K)") (class "Default")
      (node (ref "D49") (pin "2") (pinfunction "K_2") (pintype "passive"))
      (node (ref "SW49") (pin "2") (pinfunction "2_2") (pintype "passive"))
    )
    (net (code "53") (name "Net-(D50-K)") (class "Default")
      (node (ref "D50") (pin "2") (pinfunction "K_2") (pintype "passive"))
      (node (ref "SW50") (pin "2") (pinfunction "2_2") (pintype "passive"))
    )
    (net (code "54") (name "Net-(D51-A)") (class "Default")
      (node (ref "D51") (pin "1") (pinfunction "A_1") (pintype "passive"))
      (node (ref "D52") (pin "1") (pinfunction "A_1") (pintype "passive"))
      (node (ref "D53") (pin "1") (pinfunction "A_1") (pintype "passive"))
      (node (ref "D54") (pin "1") (pinfunction "A_1") (pintype "passive"))
      (node (ref "D55") (pin "1") (pinfunction "A_1") (pintype "passive"))
      (node (ref "D56") (pin "1") (pinfunction "A_1") (pintype "passive"))
      (node (ref "D57") (pin "1") (pinfunction "A_1") (pintype "passive"))
      (node (ref "D58") (pin "1") (pinfunction "A_1") (pintype "passive"))
      (node (ref "D59") (pin "1") (pinfunction "A_1") (pintype "passive"))
      (node (ref "D60") (pin "1") (pinfunction "A_1") (pintype "passive"))
      (node (ref "D61") (pin "1") (pinfunction "A_1") (pintype "passive"))
      (node (ref "D62") (pin "1") (pinfunction "A_1") (pintype "passive"))
      (node (ref "D63") (pin "1") (pinfunction "A_1") (pintype "passive"))
    )
    (net (code "55") (name "Net-(D51-K)") (class "Default")
      (node (ref "D51") (pin "2") (pinfunction "K_2") (pintype "passive"))
      (node (ref "SW51") (pin "2") (pinfunction "2_2") (pintype "passive"))
    )
    (net (code "56") (name "Net-(D52-K)") (class "Default")
      (node (ref "D52") (pin "2") (pinfunction "K_2") (pintype "passive"))
      (node (ref "SW52") (pin "2") (pinfunction "2_2") (pintype "passive"))
    )
    (net (code "57") (name "Net-(D53-K)") (class "Default")
      (node (ref "D53") (pin "2") (pinfunction "K_2") (pintype "passive"))
      (node (ref "SW53") (pin "2") (pinfunction "2_2") (pintype "passive"))
    )
    (net (code "58") (name "Net-(D54-K)") (class "Default")
      (node (ref "D54") (pin "2") (pinfunction "K_2") (pintype "passive"))
      (node (ref "SW54") (pin "2") (pinfunction "2_2") (pintype "passive"))
    )
    (net (code "59") (name "Net-(D55-K)") (class "Default")
      (node (ref "D55") (pin "2") (pinfunction "K_2") (pintype "passive"))
      (node (ref "SW55") (pin "2") (pinfunction "2_2") (pintype "passive"))
    )
    (net (code "60") (name "Net-(D56-K)") (class "Default")
      (node (ref "D56") (pin "2") (pinfunction "K_2") (pintype "passive"))
      (node (ref "SW56") (pin "2") (pinfunction "2_2") (pintype "passive"))
    )
    (net (code "61") (name "Net-(D57-K)") (class "Default")
      (node (ref "D57") (pin "2") (pinfunction "K_2") (pintype "passive"))
      (node (ref "SW57") (pin "2") (pinfunction "2_2") (pintype "passive"))
    )
    (net (code "62") (name "Net-(D58-K)") (class "Default")
      (node (ref "D58") (pin "2") (pinfunction "K_2") (pintype "passive"))
      (node (ref "SW58") (pin "2") (pinfunction "2_2") (pintype "passive"))
    )
    (net (code "63") (name "Net-(D59-K)") (class "Default")
      (node (ref "D59") (pin "2") (pinfunction "K_2") (pintype "passive"))
      (node (ref "SW59") (pin "2") (pinfunction "2_2") (pintype "passive"))
    )
    (net (code "64") (name "Net-(D60-K)") (class "Default")
      (node (ref "D60") (pin "2") (pinfunction "K_2") (pintype "passive"))
      (node (ref "SW60") (pin "2") (pinfunction "2_2") (pintype "passive"))
    )
    (net (code "65") (name "Net-(D61-K)") (class "Default")
      (node (ref "D61") (pin "2") (pinfunction "K_2") (pintype "passive"))
      (node (ref "SW61") (pin "2") (pinfunction "2_2") (pintype "passive"))
    )
    (net (code "66") (name "Net-(D62-K)") (class "Default")
      (node (ref "D62") (pin "2") (pinfunction "K_2") (pintype "passive"))
      (node (ref "SW62") (pin "2") (pinfunction "2_2") (pintype "passive"))
    )
    (net (code "67") (name "Net-(D63-K)") (class "Default")
      (node (ref "D63") (pin "2") (pinfunction "K_2") (pintype "passive"))
      (node (ref "SW63") (pin "2") (pinfunction "2_2") (pintype "passive"))
    )
    (net (code "68") (name "Net-(D64-A)") (class "Default")
      (node (ref "D64") (pin "1") (pinfunction "A_1") (pintype "passive"))
      (node (ref "D65") (pin "1") (pinfunction "A_1") (pintype "passive"))
      (node (ref "D66") (pin "1") (pinfunction "A_1") (pintype "passive"))
      (node (ref "D67") (pin "1") (pinfunction "A_1") (pintype "passive"))
      (node (ref "D68") (pin "1") (pinfunction "A_1") (pintype "passive"))
      (node (ref "D69") (pin "1") (pinfunction "A_1") (pintype "passive"))
      (node (ref "D70") (pin "1") (pinfunction "A_1") (pintype "passive"))
      (node (ref "D71") (pin "1") (pinfunction "A_1") (pintype "passive"))
      (node (ref "D72") (pin "1") (pinfunction "A_1") (pintype "passive"))
      (node (ref "D73") (pin "1") (pinfunction "A_1") (pintype "passive"))
      (node (ref "D74") (pin "1") (pinfunction "A_1") (pintype "passive"))
      (node (ref "D75") (pin "1") (pinfunction "A_1") (pintype "passive"))
      (node (ref "D76") (pin "1") (pinfunction "A_1") (pintype "passive"))
    )
    (net (code "69") (name "Net-(D64-K)") (class "Default")
      (node (ref "D64") (pin "2") (pinfunction "K_2") (pintype "passive"))
      (node (ref "SW64") (pin "2") (pinfunction "2_2") (pintype "passive"))
    )
    (net (code "70") (name "Net-(D65-K)") (class "Default")
      (node (ref "D65") (pin "2") (pinfunction "K_2") (pintype "passive"))
      (node (ref "SW65") (pin "2") (pinfunction "2_2") (pintype "passive"))
    )
    (net (code "71") (name "Net-(D66-K)") (class "Default")
      (node (ref "D66") (pin "2") (pinfunction "K_2") (pintype "passive"))
      (node (ref "SW66") (pin "2") (pinfunction "2_2") (pintype "passive"))
    )
    (net (code "72") (name "Net-(D67-K)") (class "Default")
      (node (ref "D67") (pin "2") (pinfunction "K_2") (pintype "passive"))
      (node (ref "SW67") (pin "2") (pinfunction "2_2") (pintype "passive"))
    )
    (net (code "73") (name "Net-(D68-K)") (class "Default")
      (node (ref "D68") (pin "2") (pinfunction "K_2") (pintype "passive"))
      (node (ref "SW68") (pin "2") (pinfunction "2_2") (pintype "passive"))
    )
    (net (code "74") (name "Net-(D69-K)") (class "Default")
      (node (ref "D69") (pin "2") (pinfunction "K_2") (pintype "passive"))
      (node (ref "SW69") (pin "2") (pinfunction "2_2") (pintype "passive"))
    )
    (net (code "75") (name "Net-(D70-K)") (class "Default")
      (node (ref "D70") (pin "2") (pinfunction "K_2") (pintype "passive"))
      (node (ref "SW70") (pin "2") (pinfunction "2_2") (pintype "passive"))
    )
    (net (code "76") (name "Net-(D71-K)") (class "Default")
      (node (ref "D71") (pin "2") (pinfunction "K_2") (pintype "passive"))
      (node (ref "SW71") (pin "2") (pinfunction "2_2") (pintype "passive"))
    )
    (net (code "77") (name "Net-(D72-K)") (class "Default")
      (node (ref "D72") (pin "2") (pinfunction "K_2") (pintype "passive"))
      (node (ref "SW72") (pin "2") (pinfunction "2_2") (pintype "passive"))
    )
    (net (code "78") (name "Net-(D73-K)") (class "Default")
      (node (ref "D73") (pin "2") (pinfunction "K_2") (pintype "passive"))
      (node (ref "SW73") (pin "2") (pinfunction "2_2") (pintype "passive"))
    )
    (net (code "79") (name "Net-(D74-K)") (class "Default")
      (node (ref "D74") (pin "2") (pinfunction "K_2") (pintype "passive"))
      (node (ref "SW74") (pin "2") (pinfunction "2_2") (pintype "passive"))
    )
    (net (code "80") (name "Net-(D75-K)") (class "Default")
      (node (ref "D75") (pin "2") (pinfunction "K_2") (pintype "passive"))
      (node (ref "SW75") (pin "2") (pinfunction "2_2") (pintype "passive"))
    )
    (net (code "81") (name "Net-(D76-K)") (class "Default")
      (node (ref "D76") (pin "2") (pinfunction "K_2") (pintype "passive"))
      (node (ref "SW76") (pin "2") (pinfunction "2_2") (pintype "passive"))
    )
    (net (code "82") (name "Net-(D77-A)") (class "Default")
      (node (ref "D77") (pin "1") (pinfunction "A_1") (pintype "passive"))
      (node (ref "D78") (pin "1") (pinfunction "A_1") (pintype "passive"))
      (node (ref "D79") (pin "1") (pinfunction "A_1") (pintype "passive"))
      (node (ref "D80") (pin "1") (pinfunction "A_1") (pintype "passive"))
      (node (ref "D81") (pin "1") (pinfunction "A_1") (pintype "passive"))
      (node (ref "D82") (pin "1") (pinfunction "A_1") (pintype "passive"))
      (node (ref "D83") (pin "1") (pinfunction "A_1") (pintype "passive"))
      (node (ref "D84") (pin "1") (pinfunction "A_1") (pintype "passive"))
      (node (ref "D85") (pin "1") (pinfunction "A_1") (pintype "passive"))
      (node (ref "D86") (pin "1") (pinfunction "A_1") (pintype "passive"))
      (node (ref "D87") (pin "1") (pinfunction "A_1") (pintype "passive"))
    )
    (net (code "83") (name "Net-(D77-K)") (class "Default")
      (node (ref "D77") (pin "2") (pinfunction "K_2") (pintype "passive"))
      (node (ref "SW77") (pin "2") (pinfunction "2_2") (pintype "passive"))
    )
    (net (code "84") (name "Net-(D78-K)") (class "Default")
      (node (ref "D78") (pin "2") (pinfunction "K_2") (pintype "passive"))
      (node (ref "SW78") (pin "2") (pinfunction "2_2") (pintype "passive"))
    )
    (net (code "85") (name "Net-(D79-K)") (class "Default")
      (node (ref "D79") (pin "2") (pinfunction "K_2") (pintype "passive"))
      (node (ref "SW79") (pin "2") (pinfunction "2_2") (pintype "passive"))
    )
    (net (code "86") (name "Net-(D80-K)") (class "Default")
      (node (ref "D80") (pin "2") (pinfunction "K_2") (pintype "passive"))
      (node (ref "SW80") (pin "2") (pinfunction "2_2") (pintype "passive"))
    )
    (net (code "87") (name "Net-(D81-K)") (class "Default")
      (node (ref "D81") (pin "2") (pinfunction "K_2") (pintype "passive"))
      (node (ref "SW81") (pin "2") (pinfunction "2_2") (pintype "passive"))
    )
    (net (code "88") (name "Net-(D82-K)") (class "Default")
      (node (ref "D82") (pin "2") (pinfunction "K_2") (pintype "passive"))
      (node (ref "SW82") (pin "2") (pinfunction "2_2") (pintype "passive"))
    )
    (net (code "89") (name "Net-(D83-K)") (class "Default")
      (node (ref "D83") (pin "2") (pinfunction "K_2") (pintype "passive"))
      (node (ref "SW83") (pin "2") (pinfunction "2_2") (pintype "passive"))
    )
    (net (code "90") (name "Net-(D84-K)") (class "Default")
      (node (ref "D84") (pin "2") (pinfunction "K_2") (pintype "passive"))
      (node (ref "SW84") (pin "2") (pinfunction "2_2") (pintype "passive"))
    )
    (net (code "91") (name "Net-(D85-K)") (class "Default")
      (node (ref "D85") (pin "2") (pinfunction "K_2") (pintype "passive"))
      (node (ref "SW85") (pin "2") (pinfunction "2_2") (pintype "passive"))
    )
    (net (code "92") (name "Net-(D86-K)") (class "Default")
      (node (ref "D86") (pin "2") (pinfunction "K_2") (pintype "passive"))
      (node (ref "SW86") (pin "2") (pinfunction "2_2") (pintype "passive"))
    )
    (net (code "93") (name "Net-(D87-K)") (class "Default")
      (node (ref "D87") (pin "2") (pinfunction "K_2") (pintype "passive"))
      (node (ref "SW87") (pin "2") (pinfunction "2_2") (pintype "passive"))
    )
    (net (code "94") (name "Net-(SW1-Pad1)") (class "Default")
      (node (ref "SW1") (pin "1") (pinfunction "1_1") (pintype "passive"))
      (node (ref "SW17") (pin "1") (pinfunction "1_1") (pintype "passive"))
      (node (ref "SW34") (pin "1") (pinfunction "1_1") (pintype "passive"))
      (node (ref "SW51") (pin "1") (pinfunction "1_1") (pintype "passive"))
      (node (ref "SW64") (pin "1") (pinfunction "1_1") (pintype "passive"))
      (node (ref "SW77") (pin "1") (pinfunction "1_1") (pintype "passive"))
    )
    (net (code "95") (name "Net-(SW1-Pad3)") (class "Default")
      (node (ref "SW1") (pin "3") (pinfunction "3_3") (pintype "passive"))
      (node (ref "SW17") (pin "3") (pinfunction "3_3") (pintype "passive"))
      (node (ref "SW34") (pin "3") (pinfunction "3_3") (pintype "passive"))
      (node (ref "SW51") (pin "3") (pinfunction "3_3") (pintype "passive"))
      (node (ref "SW64") (pin "3") (pinfunction "3_3") (pintype "passive"))
      (node (ref "SW77") (pin "3") (pinfunction "3_3") (pintype "passive"))
    )
    (net (code "96") (name "Net-(SW1-Pad4)") (class "Default")
      (node (ref "SW1") (pin "4") (pinfunction "4_4") (pintype "passive"))
      (node (ref "SW10") (pin "4") (pinfunction "4_4") (pintype "passive"))
      (node (ref "SW11") (pin "4") (pinfunction "4_4") (pintype "passive"))
      (node (ref "SW12") (pin "4") (pinfunction "4_4") (pintype "passive"))
      (node (ref "SW13") (pin "4") (pinfunction "4_4") (pintype "passive"))
      (node (ref "SW14") (pin "4") (pinfunction "4_4") (pintype "passive"))
      (node (ref "SW15") (pin "4") (pinfunction "4_4") (pintype "passive"))
      (node (ref "SW16") (pin "4") (pinfunction "4_4") (pintype "passive"))
      (node (ref "SW2") (pin "4") (pinfunction "4_4") (pintype "passive"))
      (node (ref "SW3") (pin "4") (pinfunction "4_4") (pintype "passive"))
      (node (ref "SW4") (pin "4") (pinfunction "4_4") (pintype "passive"))
      (node (ref "SW5") (pin "4") (pinfunction "4_4") (pintype "passive"))
      (node (ref "SW6") (pin "4") (pinfunction "4_4") (pintype "passive"))
      (node (ref "SW7") (pin "4") (pinfunction "4_4") (pintype "passive"))
      (node (ref "SW8") (pin "4") (pinfunction "4_4") (pintype "passive"))
      (node (ref "SW9") (pin "4") (pinfunction "4_4") (pintype "passive"))
    )
    (net (code "97") (name "Net-(SW10-Pad1)") (class "Default")
      (node (ref "SW10") (pin "1") (pinfunction "1_1") (pintype "passive"))
      (node (ref "SW27") (pin "1") (pinfunction "1_1") (pintype "passive"))
      (node (ref "SW44") (pin "1") (pinfunction "1_1") (pintype "passive"))
      (node (ref "SW61") (pin "1") (pinfunction "1_1") (pintype "passive"))
      (node (ref "SW74") (pin "1") (pinfunction "1_1") (pintype "passive"))
      (node (ref "SW81") (pin "1") (pinfunction "1_1") (pintype "passive"))
    )
    (net (code "98") (name "Net-(SW10-Pad3)") (class "Default")
      (node (ref "SW10") (pin "3") (pinfunction "3_3") (pintype "passive"))
      (node (ref "SW27") (pin "3") (pinfunction "3_3") (pintype "passive"))
      (node (ref "SW44") (pin "3") (pinfunction "3_3") (pintype "passive"))
      (node (ref "SW61") (pin "3") (pinfunction "3_3") (pintype "passive"))
      (node (ref "SW74") (pin "3") (pinfunction "3_3") (pintype "passive"))
      (node (ref "SW81") (pin "3") (pinfunction "3_3") (pintype "passive"))
    )
    (net (code "99") (name "Net-(SW11-Pad1)") (class "Default")
      (node (ref "SW11") (pin "1") (pinfunction "1_1") (pintype "passive"))
      (node (ref "SW28") (pin "1") (pinfunction "1_1") (pintype "passive"))
      (node (ref "SW45") (pin "1") (pinfunction "1_1") (pintype "passive"))
      (node (ref "SW62") (pin "1") (pinfunction "1_1") (pintype "passive"))
      (node (ref "SW75") (pin "1") (pinfunction "1_1") (pintype "passive"))
      (node (ref "SW82") (pin "1") (pinfunction "1_1") (pintype "passive"))
    )
    (net (code "100") (name "Net-(SW11-Pad3)") (class "Default")
      (node (ref "SW11") (pin "3") (pinfunction "3_3") (pintype "passive"))
      (node (ref "SW28") (pin "3") (pinfunction "3_3") (pintype "passive"))
      (node (ref "SW45") (pin "3") (pinfunction "3_3") (pintype "passive"))
      (node (ref "SW62") (pin "3") (pinfunction "3_3") (pintype "passive"))
      (node (ref "SW75") (pin "3") (pinfunction "3_3") (pintype "passive"))
      (node (ref "SW82") (pin "3") (pinfunction "3_3") (pintype "passive"))
    )
    (net (code "101") (name "Net-(SW12-Pad1)") (class "Default")
      (node (ref "SW12") (pin "1") (pinfunction "1_1") (pintype "passive"))
      (node (ref "SW29") (pin "1") (pinfunction "1_1") (pintype "passive"))
      (node (ref "SW46") (pin "1") (pinfunction "1_1") (pintype "passive"))
      (node (ref "SW63") (pin "1") (pinfunction "1_1") (pintype "passive"))
      (node (ref "SW83") (pin "1") (pinfunction "1_1") (pintype "passive"))
    )
    (net (code "102") (name "Net-(SW12-Pad3)") (class "Default")
      (node (ref "SW12") (pin "3") (pinfunction "3_3") (pintype "passive"))
      (node (ref "SW29") (pin "3") (pinfunction "3_3") (pintype "passive"))
      (node (ref "SW46") (pin "3") (pinfunction "3_3") (pintype "passive"))
      (node (ref "SW63") (pin "3") (pinfunction "3_3") (pintype "passive"))
      (node (ref "SW83") (pin "3") (pinfunction "3_3") (pintype "passive"))
    )
    (net (code "103") (name "Net-(SW13-Pad1)") (class "Default")
      (node (ref "SW13") (pin "1") (pinfunction "1_1") (pintype "passive"))
      (node (ref "SW30") (pin "1") (pinfunction "1_1") (pintype "passive"))
      (node (ref "SW47") (pin "1") (pinfunction "1_1") (pintype "passive"))
      (node (ref "SW84") (pin "1") (pinfunction "1_1") (pintype "passive"))
    )
    (net (code "104") (name "Net-(SW13-Pad3)") (class "Default")
      (node (ref "SW13") (pin "3") (pinfunction "3_3") (pintype "passive"))
      (node (ref "SW30") (pin "3") (pinfunction "3_3") (pintype "passive"))
      (node (ref "SW47") (pin "3") (pinfunction "3_3") (pintype "passive"))
      (node (ref "SW84") (pin "3") (pinfunction "3_3") (pintype "passive"))
    )
    (net (code "105") (name "Net-(SW14-Pad1)") (class "Default")
      (node (ref "SW14") (pin "1") (pinfunction "1_1") (pintype "passive"))
      (node (ref "SW31") (pin "1") (pinfunction "1_1") (pintype "passive"))
      (node (ref "SW48") (pin "1") (pinfunction "1_1") (pintype "passive"))
      (node (ref "SW85") (pin "1") (pinfunction "1_1") (pintype "passive"))
    )
    (net (code "106") (name "Net-(SW14-Pad3)") (class "Default")
      (node (ref "SW14") (pin "3") (pinfunction "3_3") (pintype "passive"))
      (node (ref "SW31") (pin "3") (pinfunction "3_3") (pintype "passive"))
      (node (ref "SW48") (pin "3") (pinfunction "3_3") (pintype "passive"))
      (node (ref "SW85") (pin "3") (pinfunction "3_3") (pintype "passive"))
    )
    (net (code "107") (name "Net-(SW15-Pad1)") (class "Default")
      (node (ref "SW15") (pin "1") (pinfunction "1_1") (pintype "passive"))
      (node (ref "SW32") (pin "1") (pinfunction "1_1") (pintype "passive"))
      (node (ref "SW49") (pin "1") (pinfunction "1_1") (pintype "passive"))
      (node (ref "SW76") (pin "1") (pinfunction "1_1") (pintype "passive"))
      (node (ref "SW86") (pin "1") (pinfunction "1_1") (pintype "passive"))
    )
    (net (code "108") (name "Net-(SW15-Pad3)") (class "Default")
      (node (ref "SW15") (pin "3") (pinfunction "3_3") (pintype "passive"))
      (node (ref "SW32") (pin "3") (pinfunction "3_3") (pintype "passive"))
      (node (ref "SW49") (pin "3") (pinfunction "3_3") (pintype "passive"))
      (node (ref "SW76") (pin "3") (pinfunction "3_3") (pintype "passive"))
      (node (ref "SW86") (pin "3") (pinfunction "3_3") (pintype "passive"))
    )
    (net (code "109") (name "Net-(SW16-Pad1)") (class "Default")
      (node (ref "SW16") (pin "1") (pinfunction "1_1") (pintype "passive"))
      (node (ref "SW33") (pin "1") (pinfunction "1_1") (pintype "passive"))
      (node (ref "SW50") (pin "1") (pinfunction "1_1") (pintype "passive"))
      (node (ref "SW87") (pin "1") (pinfunction "1_1") (pintype "passive"))
    )
    (net (code "110") (name "Net-(SW16-Pad3)") (class "Default")
      (node (ref "SW16") (pin "3") (pinfunction "3_3") (pintype "passive"))
      (node (ref "SW33") (pin "3") (pinfunction "3_3") (pintype "passive"))
      (node (ref "SW50") (pin "3") (pinfunction "3_3") (pintype "passive"))
      (node (ref "SW87") (pin "3") (pinfunction "3_3") (pintype "passive"))
    )
    (net (code "111") (name "Net-(SW17-Pad4)") (class "Default")
      (node (ref "SW17") (pin "4") (pinfunction "4_4") (pintype "passive"))
      (node (ref "SW18") (pin "4") (pinfunction "4_4") (pintype "passive"))
      (node (ref "SW19") (pin "4") (pinfunction "4_4") (pintype "passive"))
      (node (ref "SW20") (pin "4") (pinfunction "4_4") (pintype "passive"))
      (node (ref "SW21") (pin "4") (pinfunction "4_4") (pintype "passive"))
      (node (ref "SW22") (pin "4") (pinfunction "4_4") (pintype "passive"))
      (node (ref "SW23") (pin "4") (pinfunction "4_4") (pintype "passive"))
      (node (ref "SW24") (pin "4") (pinfunction "4_4") (pintype "passive"))
      (node (ref "SW25") (pin "4") (pinfunction "4_4") (pintype "passive"))
      (node (ref "SW26") (pin "4") (pinfunction "4_4") (pintype "passive"))
      (node (ref "SW27") (pin "4") (pinfunction "4_4") (pintype "passive"))
      (node (ref "SW28") (pin "4") (pinfunction "4_4") (pintype "passive"))
      (node (ref "SW29") (pin "4") (pinfunction "4_4") (pintype "passive"))
      (node (ref "SW30") (pin "4") (pinfunction "4_4") (pintype "passive"))
      (node (ref "SW31") (pin "4") (pinfunction "4_4") (pintype "passive"))
      (node (ref "SW32") (pin "4") (pinfunction "4_4") (pintype "passive"))
      (node (ref "SW33") (pin "4") (pinfunction "4_4") (pintype "passive"))
    )
    (net (code "112") (name "Net-(SW18-Pad1)") (class "Default")
      (node (ref "SW18") (pin "1") (pinfunction "1_1") (pintype "passive"))
      (node (ref "SW35") (pin "1") (pinfunction "1_1") (pintype "passive"))
      (node (ref "SW52") (pin "1") (pinfunction "1_1") (pintype "passive"))
      (node (ref "SW65") (pin "1") (pinfunction "1_1") (pintype "passive"))
      (node (ref "SW78") (pin "1") (pinfunction "1_1") (pintype "passive"))
    )
    (net (code "113") (name "Net-(SW18-Pad3)") (class "Default")
      (node (ref "SW18") (pin "3") (pinfunction "3_3") (pintype "passive"))
      (node (ref "SW35") (pin "3") (pinfunction "3_3") (pintype "passive"))
      (node (ref "SW52") (pin "3") (pinfunction "3_3") (pintype "passive"))
      (node (ref "SW65") (pin "3") (pinfunction "3_3") (pintype "passive"))
      (node (ref "SW78") (pin "3") (pinfunction "3_3") (pintype "passive"))
    )
    (net (code "114") (name "Net-(SW19-Pad1)") (class "Default")
      (node (ref "SW19") (pin "1") (pinfunction "1_1") (pintype "passive"))
      (node (ref "SW2") (pin "1") (pinfunction "1_1") (pintype "passive"))
      (node (ref "SW36") (pin "1") (pinfunction "1_1") (pintype "passive"))
      (node (ref "SW53") (pin "1") (pinfunction "1_1") (pintype "passive"))
      (node (ref "SW66") (pin "1") (pinfunction "1_1") (pintype "passive"))
      (node (ref "SW79") (pin "1") (pinfunction "1_1") (pintype "passive"))
    )
    (net (code "115") (name "Net-(SW19-Pad3)") (class "Default")
      (node (ref "SW19") (pin "3") (pinfunction "3_3") (pintype "passive"))
      (node (ref "SW2") (pin "3") (pinfunction "3_3") (pintype "passive"))
      (node (ref "SW36") (pin "3") (pinfunction "3_3") (pintype "passive"))
      (node (ref "SW53") (pin "3") (pinfunction "3_3") (pintype "passive"))
      (node (ref "SW66") (pin "3") (pinfunction "3_3") (pintype "passive"))
      (node (ref "SW79") (pin "3") (pinfunction "3_3") (pintype "passive"))
    )
    (net (code "116") (name "Net-(SW20-Pad1)") (class "Default")
      (node (ref "SW20") (pin "1") (pinfunction "1_1") (pintype "passive"))
      (node (ref "SW3") (pin "1") (pinfunction "1_1") (pintype "passive"))
      (node (ref "SW37") (pin "1") (pinfunction "1_1") (pintype "passive"))
      (node (ref "SW54") (pin "1") (pinfunction "1_1") (pintype "passive"))
      (node (ref "SW67") (pin "1") (pinfunction "1_1") (pintype "passive"))
      (node (ref "SW80") (pin "1") (pinfunction "1_1") (pintype "passive"))
    )
    (net (code "117") (name "Net-(SW20-Pad3)") (class "Default")
      (node (ref "SW20") (pin "3") (pinfunction "3_3") (pintype "passive"))
      (node (ref "SW3") (pin "3") (pinfunction "3_3") (pintype "passive"))
      (node (ref "SW37") (pin "3") (pinfunction "3_3") (pintype "passive"))
      (node (ref "SW54") (pin "3") (pinfunction "3_3") (pintype "passive"))
      (node (ref "SW67") (pin "3") (pinfunction "3_3") (pintype "passive"))
      (node (ref "SW80") (pin "3") (pinfunction "3_3") (pintype "passive"))
    )
    (net (code "118") (name "Net-(SW21-Pad1)") (class "Default")
      (node (ref "SW21") (pin "1") (pinfunction "1_1") (pintype "passive"))
      (node (ref "SW38") (pin "1") (pinfunction "1_1") (pintype "passive"))
      (node (ref "SW4") (pin "1") (pinfunction "1_1") (pintype "passive"))
      (node (ref "SW55") (pin "1") (pinfunction "1_1") (pintype "passive"))
      (node (ref "SW68") (pin "1") (pinfunction "1_1") (pintype "passive"))
    )
    (net (code "119") (name "Net-(SW21-Pad3)") (class "Default")
      (node (ref "SW21") (pin "3") (pinfunction "3_3") (pintype "passive"))
      (node (ref "SW38") (pin "3") (pinfunction "3_3") (pintype "passive"))
      (node (ref "SW4") (pin "3") (pinfunction "3_3") (pintype "passive"))
      (node (ref "SW55") (pin "3") (pinfunction "3_3") (pintype "passive"))
      (node (ref "SW68") (pin "3") (pinfunction "3_3") (pintype "passive"))
    )
    (net (code "120") (name "Net-(SW22-Pad1)") (class "Default")
      (node (ref "SW22") (pin "1") (pinfunction "1_1") (pintype "passive"))
      (node (ref "SW39") (pin "1") (pinfunction "1_1") (pintype "passive"))
      (node (ref "SW5") (pin "1") (pinfunction "1_1") (pintype "passive"))
      (node (ref "SW56") (pin "1") (pinfunction "1_1") (pintype "passive"))
      (node (ref "SW69") (pin "1") (pinfunction "1_1") (pintype "passive"))
    )
    (net (code "121") (name "Net-(SW22-Pad3)") (class "Default")
      (node (ref "SW22") (pin "3") (pinfunction "3_3") (pintype "passive"))
      (node (ref "SW39") (pin "3") (pinfunction "3_3") (pintype "passive"))
      (node (ref "SW5") (pin "3") (pinfunction "3_3") (pintype "passive"))
      (node (ref "SW56") (pin "3") (pinfunction "3_3") (pintype "passive"))
      (node (ref "SW69") (pin "3") (pinfunction "3_3") (pintype "passive"))
    )
    (net (code "122") (name "Net-(SW23-Pad1)") (class "Default")
      (node (ref "SW23") (pin "1") (pinfunction "1_1") (pintype "passive"))
      (node (ref "SW40") (pin "1") (pinfunction "1_1") (pintype "passive"))
      (node (ref "SW57") (pin "1") (pinfunction "1_1") (pintype "passive"))
      (node (ref "SW6") (pin "1") (pinfunction "1_1") (pintype "passive"))
      (node (ref "SW70") (pin "1") (pinfunction "1_1") (pintype "passive"))
    )
    (net (code "123") (name "Net-(SW23-Pad3)") (class "Default")
      (node (ref "SW23") (pin "3") (pinfunction "3_3") (pintype "passive"))
      (node (ref "SW40") (pin "3") (pinfunction "3_3") (pintype "passive"))
      (node (ref "SW57") (pin "3") (pinfunction "3_3") (pintype "passive"))
      (node (ref "SW6") (pin "3") (pinfunction "3_3") (pintype "passive"))
      (node (ref "SW70") (pin "3") (pinfunction "3_3") (pintype "passive"))
    )
    (net (code "124") (name "Net-(SW24-Pad1)") (class "Default")
      (node (ref "SW24") (pin "1") (pinfunction "1_1") (pintype "passive"))
      (node (ref "SW41") (pin "1") (pinfunction "1_1") (pintype "passive"))
      (node (ref "SW58") (pin "1") (pinfunction "1_1") (pintype "passive"))
      (node (ref "SW7") (pin "1") (pinfunction "1_1") (pintype "passive"))
      (node (ref "SW71") (pin "1") (pinfunction "1_1") (pintype "passive"))
    )
    (net (code "125") (name "Net-(SW24-Pad3)") (class "Default")
      (node (ref "SW24") (pin "3") (pinfunction "3_3") (pintype "passive"))
      (node (ref "SW41") (pin "3") (pinfunction "3_3") (pintype "passive"))
      (node (ref "SW58") (pin "3") (pinfunction "3_3") (pintype "passive"))
      (node (ref "SW7") (pin "3") (pinfunction "3_3") (pintype "passive"))
      (node (ref "SW71") (pin "3") (pinfunction "3_3") (pintype "passive"))
    )
    (net (code "126") (name "Net-(SW25-Pad1)") (class "Default")
      (node (ref "SW25") (pin "1") (pinfunction "1_1") (pintype "passive"))
      (node (ref "SW42") (pin "1") (pinfunction "1_1") (pintype "passive"))
      (node (ref "SW59") (pin "1") (pinfunction "1_1") (pintype "passive"))
      (node (ref "SW72") (pin "1") (pinfunction "1_1") (pintype "passive"))
      (node (ref "SW8") (pin "1") (pinfunction "1_1") (pintype "passive"))
    )
    (net (code "127") (name "Net-(SW25-Pad3)") (class "Default")
      (node (ref "SW25") (pin "3") (pinfunction "3_3") (pintype "passive"))
      (node (ref "SW42") (pin "3") (pinfunction "3_3") (pintype "passive"))
      (node (ref "SW59") (pin "3") (pinfunction "3_3") (pintype "passive"))
      (node (ref "SW72") (pin "3") (pinfunction "3_3") (pintype "passive"))
      (node (ref "SW8") (pin "3") (pinfunction "3_3") (pintype "passive"))
    )
    (net (code "128") (name "Net-(SW26-Pad1)") (class "Default")
      (node (ref "SW26") (pin "1") (pinfunction "1_1") (pintype "passive"))
      (node (ref "SW43") (pin "1") (pinfunction "1_1") (pintype "passive"))
      (node (ref "SW60") (pin "1") (pinfunction "1_1") (pintype "passive"))
      (node (ref "SW73") (pin "1") (pinfunction "1_1") (pintype "passive"))
      (node (ref "SW9") (pin "1") (pinfunction "1_1") (pintype "passive"))
    )
    (net (code "129") (name "Net-(SW26-Pad3)") (class "Default")
      (node (ref "SW26") (pin "3") (pinfunction "3_3") (pintype "passive"))
      (node (ref "SW43") (pin "3") (pinfunction "3_3") (pintype "passive"))
      (node (ref "SW60") (pin "3") (pinfunction "3_3") (pintype "passive"))
      (node (ref "SW73") (pin "3") (pinfunction "3_3") (pintype "passive"))
      (node (ref "SW9") (pin "3") (pinfunction "3_3") (pintype "passive"))
    )
    (net (code "130") (name "Net-(SW34-Pad4)") (class "Default")
      (node (ref "SW34") (pin "4") (pinfunction "4_4") (pintype "passive"))
      (node (ref "SW35") (pin "4") (pinfunction "4_4") (pintype "passive"))
      (node (ref "SW36") (pin "4") (pinfunction "4_4") (pintype "passive"))
      (node (ref "SW37") (pin "4") (pinfunction "4_4") (pintype "passive"))
      (node (ref "SW38") (pin "4") (pinfunction "4_4") (pintype "passive"))
      (node (ref "SW39") (pin "4") (pinfunction "4_4") (pintype "passive"))
      (node (ref "SW40") (pin "4") (pinfunction "4_4") (pintype "passive"))
      (node (ref "SW41") (pin "4") (pinfunction "4_4") (pintype "passive"))
      (node (ref "SW42") (pin "4") (pinfunction "4_4") (pintype "passive"))
      (node (ref "SW43") (pin "4") (pinfunction "4_4") (pintype "passive"))
      (node (ref "SW44") (pin "4") (pinfunction "4_4") (pintype "passive"))
      (node (ref "SW45") (pin "4") (pinfunction "4_4") (pintype "passive"))
      (node (ref "SW46") (pin "4") (pinfunction "4_4") (pintype "passive"))
      (node (ref "SW47") (pin "4") (pinfunction "4_4") (pintype "passive"))
      (node (ref "SW48") (pin "4") (pinfunction "4_4") (pintype "passive"))
      (node (ref "SW49") (pin "4") (pinfunction "4_4") (pintype "passive"))
      (node (ref "SW50") (pin "4") (pinfunction "4_4") (pintype "passive"))
    )
    (net (code "131") (name "Net-(SW51-Pad4)") (class "Default")
      (node (ref "SW51") (pin "4") (pinfunction "4_4") (pintype "passive"))
      (node (ref "SW52") (pin "4") (pinfunction "4_4") (pintype "passive"))
      (node (ref "SW53") (pin "4") (pinfunction "4_4") (pintype "passive"))
      (node (ref "SW54") (pin "4") (pinfunction "4_4") (pintype "passive"))
      (node (ref "SW55") (pin "4") (pinfunction "4_4") (pintype "passive"))
      (node (ref "SW56") (pin "4") (pinfunction "4_4") (pintype "passive"))
      (node (ref "SW57") (pin "4") (pinfunction "4_4") (pintype "passive"))
      (node (ref "SW58") (pin "4") (pinfunction "4_4") (pintype "passive"))
      (node (ref "SW59") (pin "4") (pinfunction "4_4") (pintype "passive"))
      (node (ref "SW60") (pin "4") (pinfunction "4_4") (pintype "passive"))
      (node (ref "SW61") (pin "4") (pinfunction "4_4") (pintype "passive"))
      (node (ref "SW62") (pin "4") (pinfunction "4_4") (pintype "passive"))
      (node (ref "SW63") (pin "4") (pinfunction "4_4") (pintype "passive"))
    )
    (net (code "132") (name "Net-(SW64-Pad4)") (class "Default")
      (node (ref "SW64") (pin "4") (pinfunction "4_4") (pintype "passive"))
      (node (ref "SW65") (pin "4") (pinfunction "4_4") (pintype "passive"))
      (node (ref "SW66") (pin "4") (pinfunction "4_4") (pintype "passive"))
      (node (ref "SW67") (pin "4") (pinfunction "4_4") (pintype "passive"))
      (node (ref "SW68") (pin "4") (pinfunction "4_4") (pintype "passive"))
      (node (ref "SW69") (pin "4") (pinfunction "4_4") (pintype "passive"))
      (node (ref "SW70") (pin "4") (pinfunction "4_4") (pintype "passive"))
      (node (ref "SW71") (pin "4") (pinfunction "4_4") (pintype "passive"))
      (node (ref "SW72") (pin "4") (pinfunction "4_4") (pintype "passive"))
      (node (ref "SW73") (pin "4") (pinfunction "4_4") (pintype "passive"))
      (node (ref "SW74") (pin "4") (pinfunction "4_4") (pintype "passive"))
      (node (ref "SW75") (pin "4") (pinfunction "4_4") (pintype "passive"))
      (node (ref "SW76") (pin "4") (pinfunction "4_4") (pintype "passive"))
    )
    (net (code "133") (name "Net-(SW77-Pad4)") (class "Default")
      (node (ref "SW77") (pin "4") (pinfunction "4_4") (pintype "passive"))
      (node (ref "SW78") (pin "4") (pinfunction "4_4") (pintype "passive"))
      (node (ref "SW79") (pin "4") (pinfunction "4_4") (pintype "passive"))
      (node (ref "SW80") (pin "4") (pinfunction "4_4") (pintype "passive"))
      (node (ref "SW81") (pin "4") (pinfunction "4_4") (pintype "passive"))
      (node (ref "SW82") (pin "4") (pinfunction "4_4") (pintype "passive"))
      (node (ref "SW83") (pin "4") (pinfunction "4_4") (pintype "passive"))
      (node (ref "SW84") (pin "4") (pinfunction "4_4") (pintype "passive"))
      (node (ref "SW85") (pin "4") (pinfunction "4_4") (pintype "passive"))
      (node (ref "SW86") (pin "4") (pinfunction "4_4") (pintype "passive"))
      (node (ref "SW87") (pin "4") (pinfunction "4_4") (pintype "passive"))
    )
    (net (code "134") (name "unconnected-(JP1-Pad1)") (class "Default")
      (node (ref "JP1") (pin "1") (pinfunction "1_1") (pintype "passive"))
    )
    (net (code "135") (name "unconnected-(JP1-Pad2)") (class "Default")
      (node (ref "JP1") (pin "2") (pinfunction "2_2") (pintype "passive"))
    )
    (net (code "136") (name "unconnected-(JP1-Pad3)") (class "Default")
      (node (ref "JP1") (pin "3") (pinfunction "3_3") (pintype "passive"))
    )
    (net (code "137") (name "unconnected-(JP1-Pad4)") (class "Default")
      (node (ref "JP1") (pin "4") (pinfunction "4_4") (pintype "passive"))
    )
    (net (code "138") (name "unconnected-(JP2-Pad1)") (class "Default")
      (node (ref "JP2") (pin "1") (pinfunction "1_1") (pintype "passive"))
    )
    (net (code "139") (name "unconnected-(JP2-Pad2)") (class "Default")
      (node (ref "JP2") (pin "2") (pinfunction "2_2") (pintype "passive"))
    )
    (net (code "140") (name "unconnected-(JP2-Pad3)") (class "Default")
      (node (ref "JP2") (pin "3") (pinfunction "3_3") (pintype "passive"))
    )
    (net (code "141") (name "unconnected-(JP2-Pad4)") (class "Default")
      (node (ref "JP2") (pin "4") (pinfunction "4_4") (pintype "passive"))
    )
    (net (code "142") (name "unconnected-(JP3-Pad1)") (class "Default")
      (node (ref "JP3") (pin "1") (pinfunction "1_1") (pintype "passive"))
    )
    (net (code "143") (name "unconnected-(JP3-Pad2)") (class "Default")
      (node (ref "JP3") (pin "2") (pinfunction "2_2") (pintype "passive"))
    )
    (net (code "144") (name "unconnected-(JP3-Pad3)") (class "Default")
      (node (ref "JP3") (pin "3") (pinfunction "3_3") (pintype "passive"))
    )
    (net (code "145") (name "unconnected-(JP3-Pad4)") (class "Default")
      (node (ref "JP3") (pin "4") (pinfunction "4_4") (pintype "passive"))
    )
    (net (code "146") (name "unconnected-(JP4-Pad1)") (class "Default")
      (node (ref "JP4") (pin "1") (pinfunction "1_1") (pintype "passive"))
    )
    (net (code "147") (name "unconnected-(JP4-Pad2)") (class "Default")
      (node (ref "JP4") (pin "2") (pinfunction "2_2") (pintype "passive"))
    )
    (net (code "148") (name "unconnected-(JP4-Pad3)") (class "Default")
      (node (ref "JP4") (pin "3") (pinfunction "3_3") (pintype "passive"))
    )
    (net (code "149") (name "unconnected-(JP4-Pad4)") (class "Default")
      (node (ref "JP4") (pin "4") (pinfunction "4_4") (pintype "passive"))
    )
    (net (code "150") (name "unconnected-(JP5-Pad1)") (class "Default")
      (node (ref "JP5") (pin "1") (pinfunction "1_1") (pintype "passive"))
    )
    (net (code "151") (name "unconnected-(JP5-Pad2)") (class "Default")
      (node (ref "JP5") (pin "2") (pinfunction "2_2") (pintype "passive"))
    )
    (net (code "152") (name "unconnected-(JP5-Pad3)") (class "Default")
      (node (ref "JP5") (pin "3") (pinfunction "3_3") (pintype "passive"))
    )
    (net (code "153") (name "unconnected-(JP5-Pad4)") (class "Default")
      (node (ref "JP5") (pin "4") (pinfunction "4_4") (pintype "passive"))
    )
  )
)
